# io-board-b-7.net
KiCad netlist of a schematic drawn in EAGLE
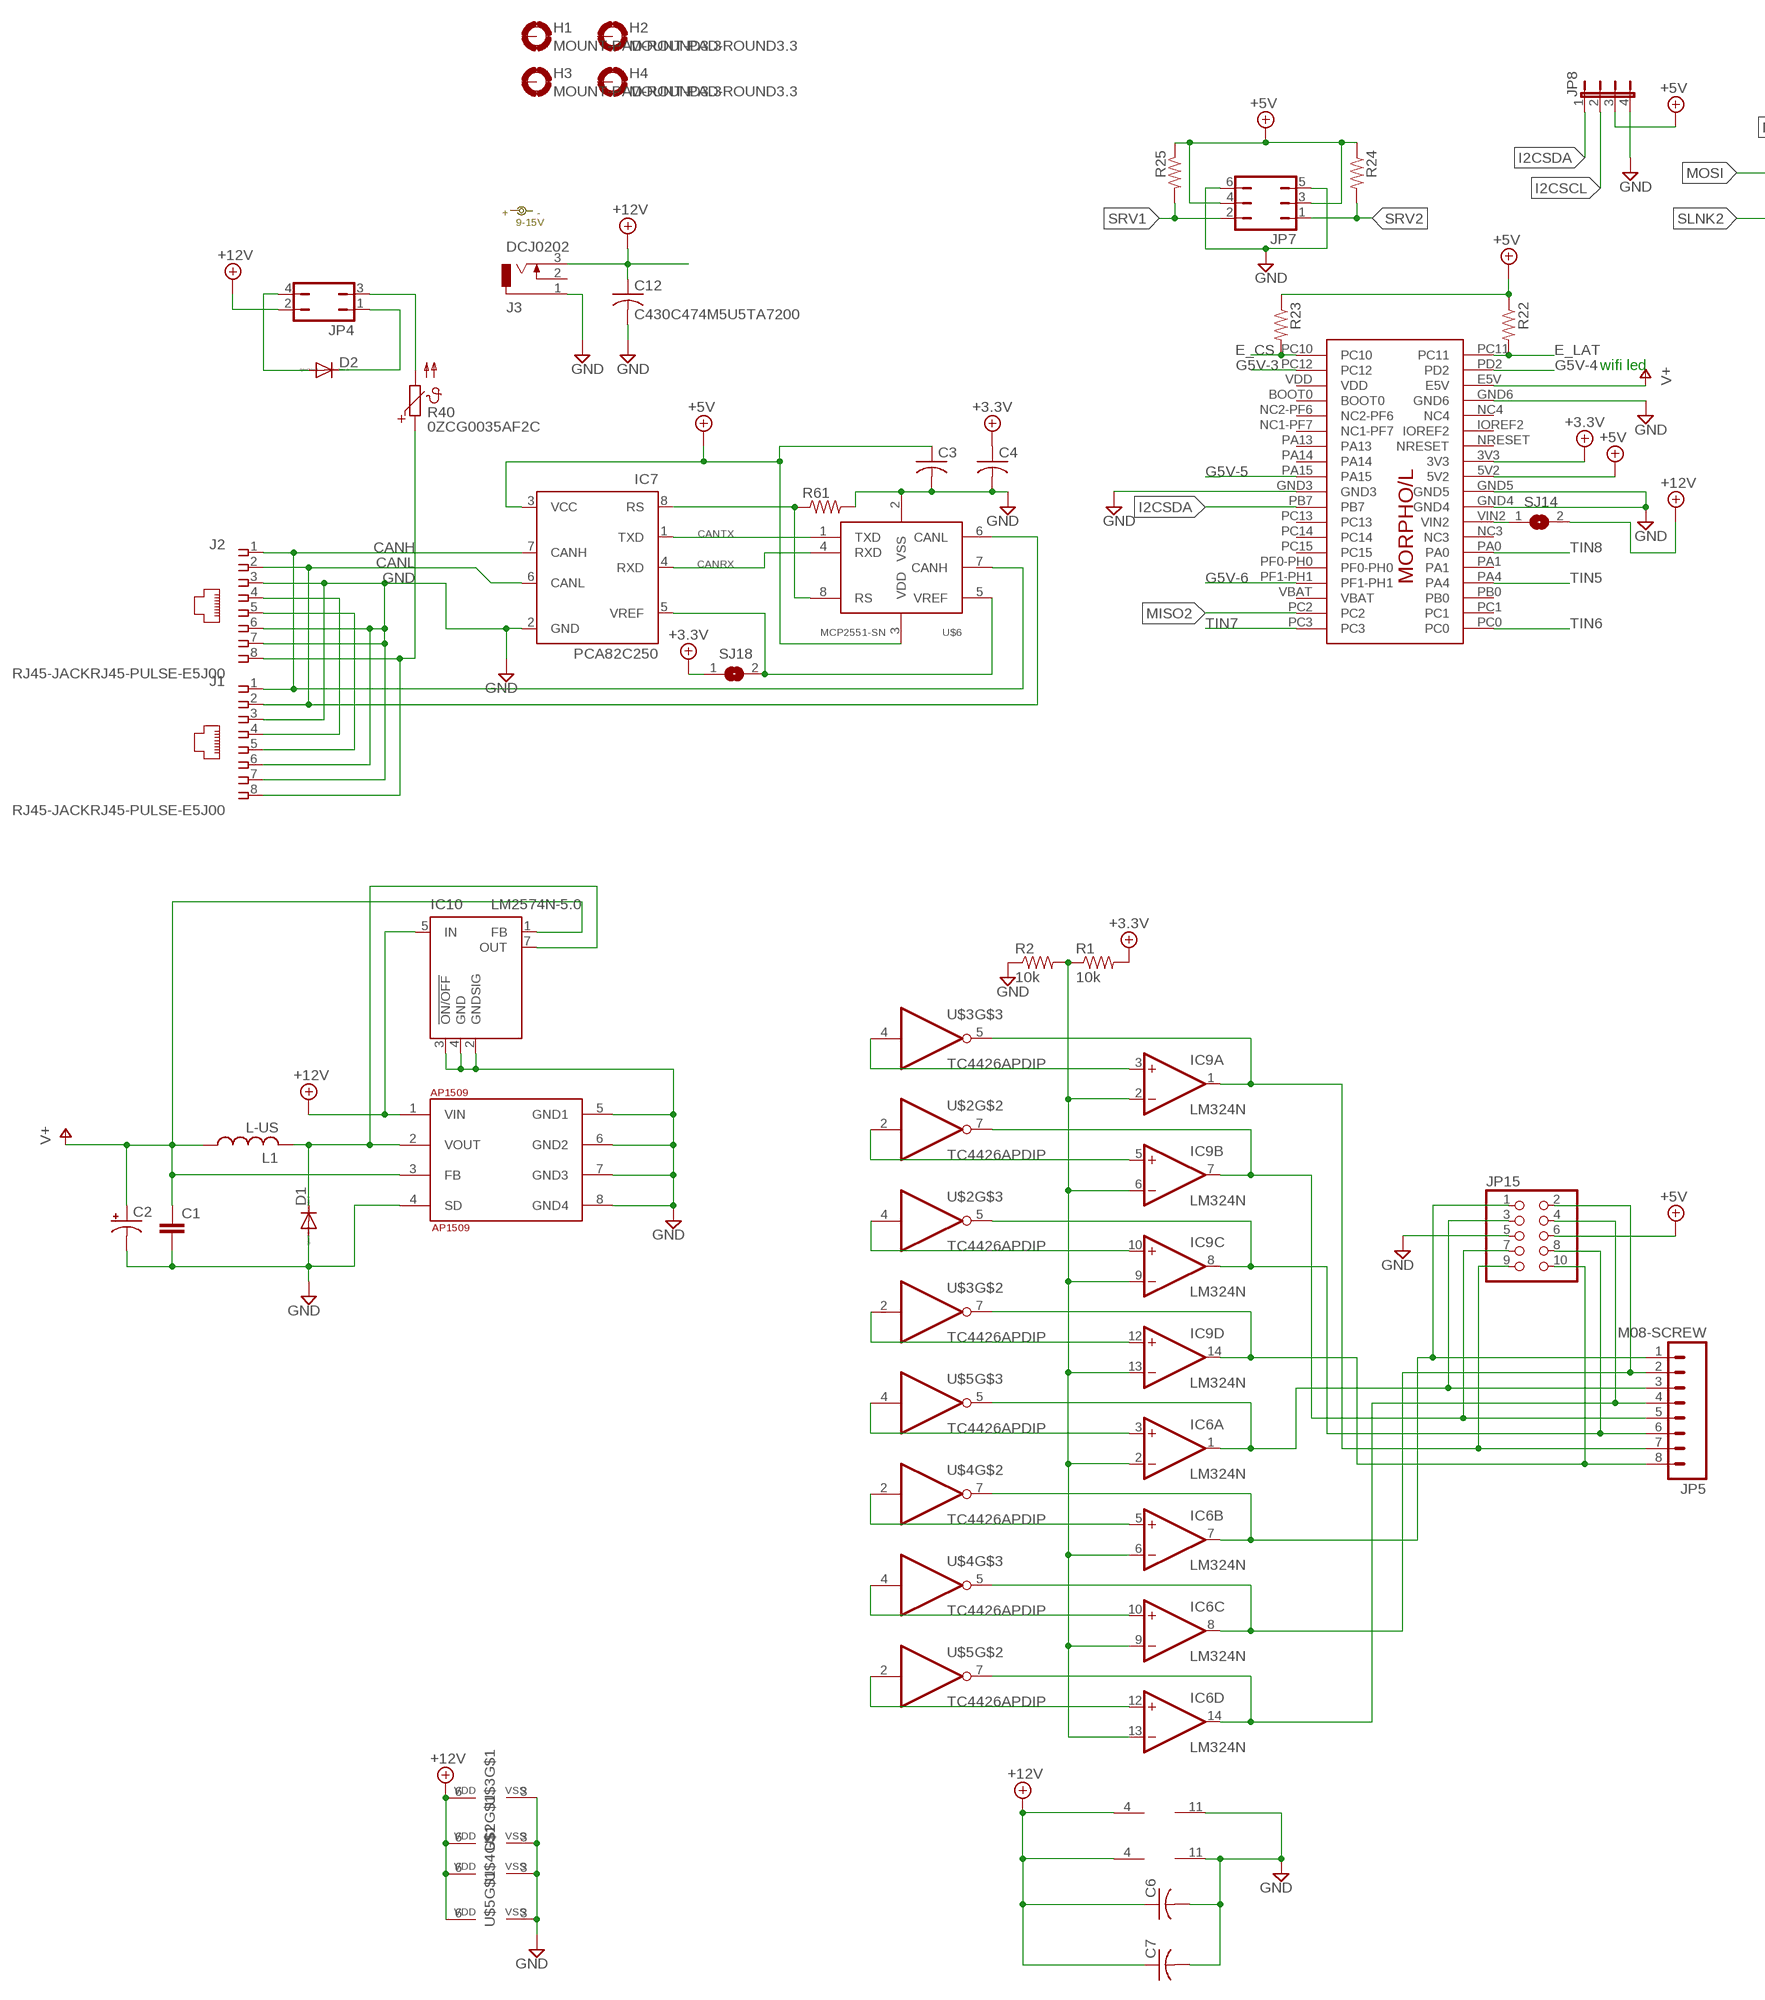
[diagram p0: schematic, sheet 1, part 1 of 2]
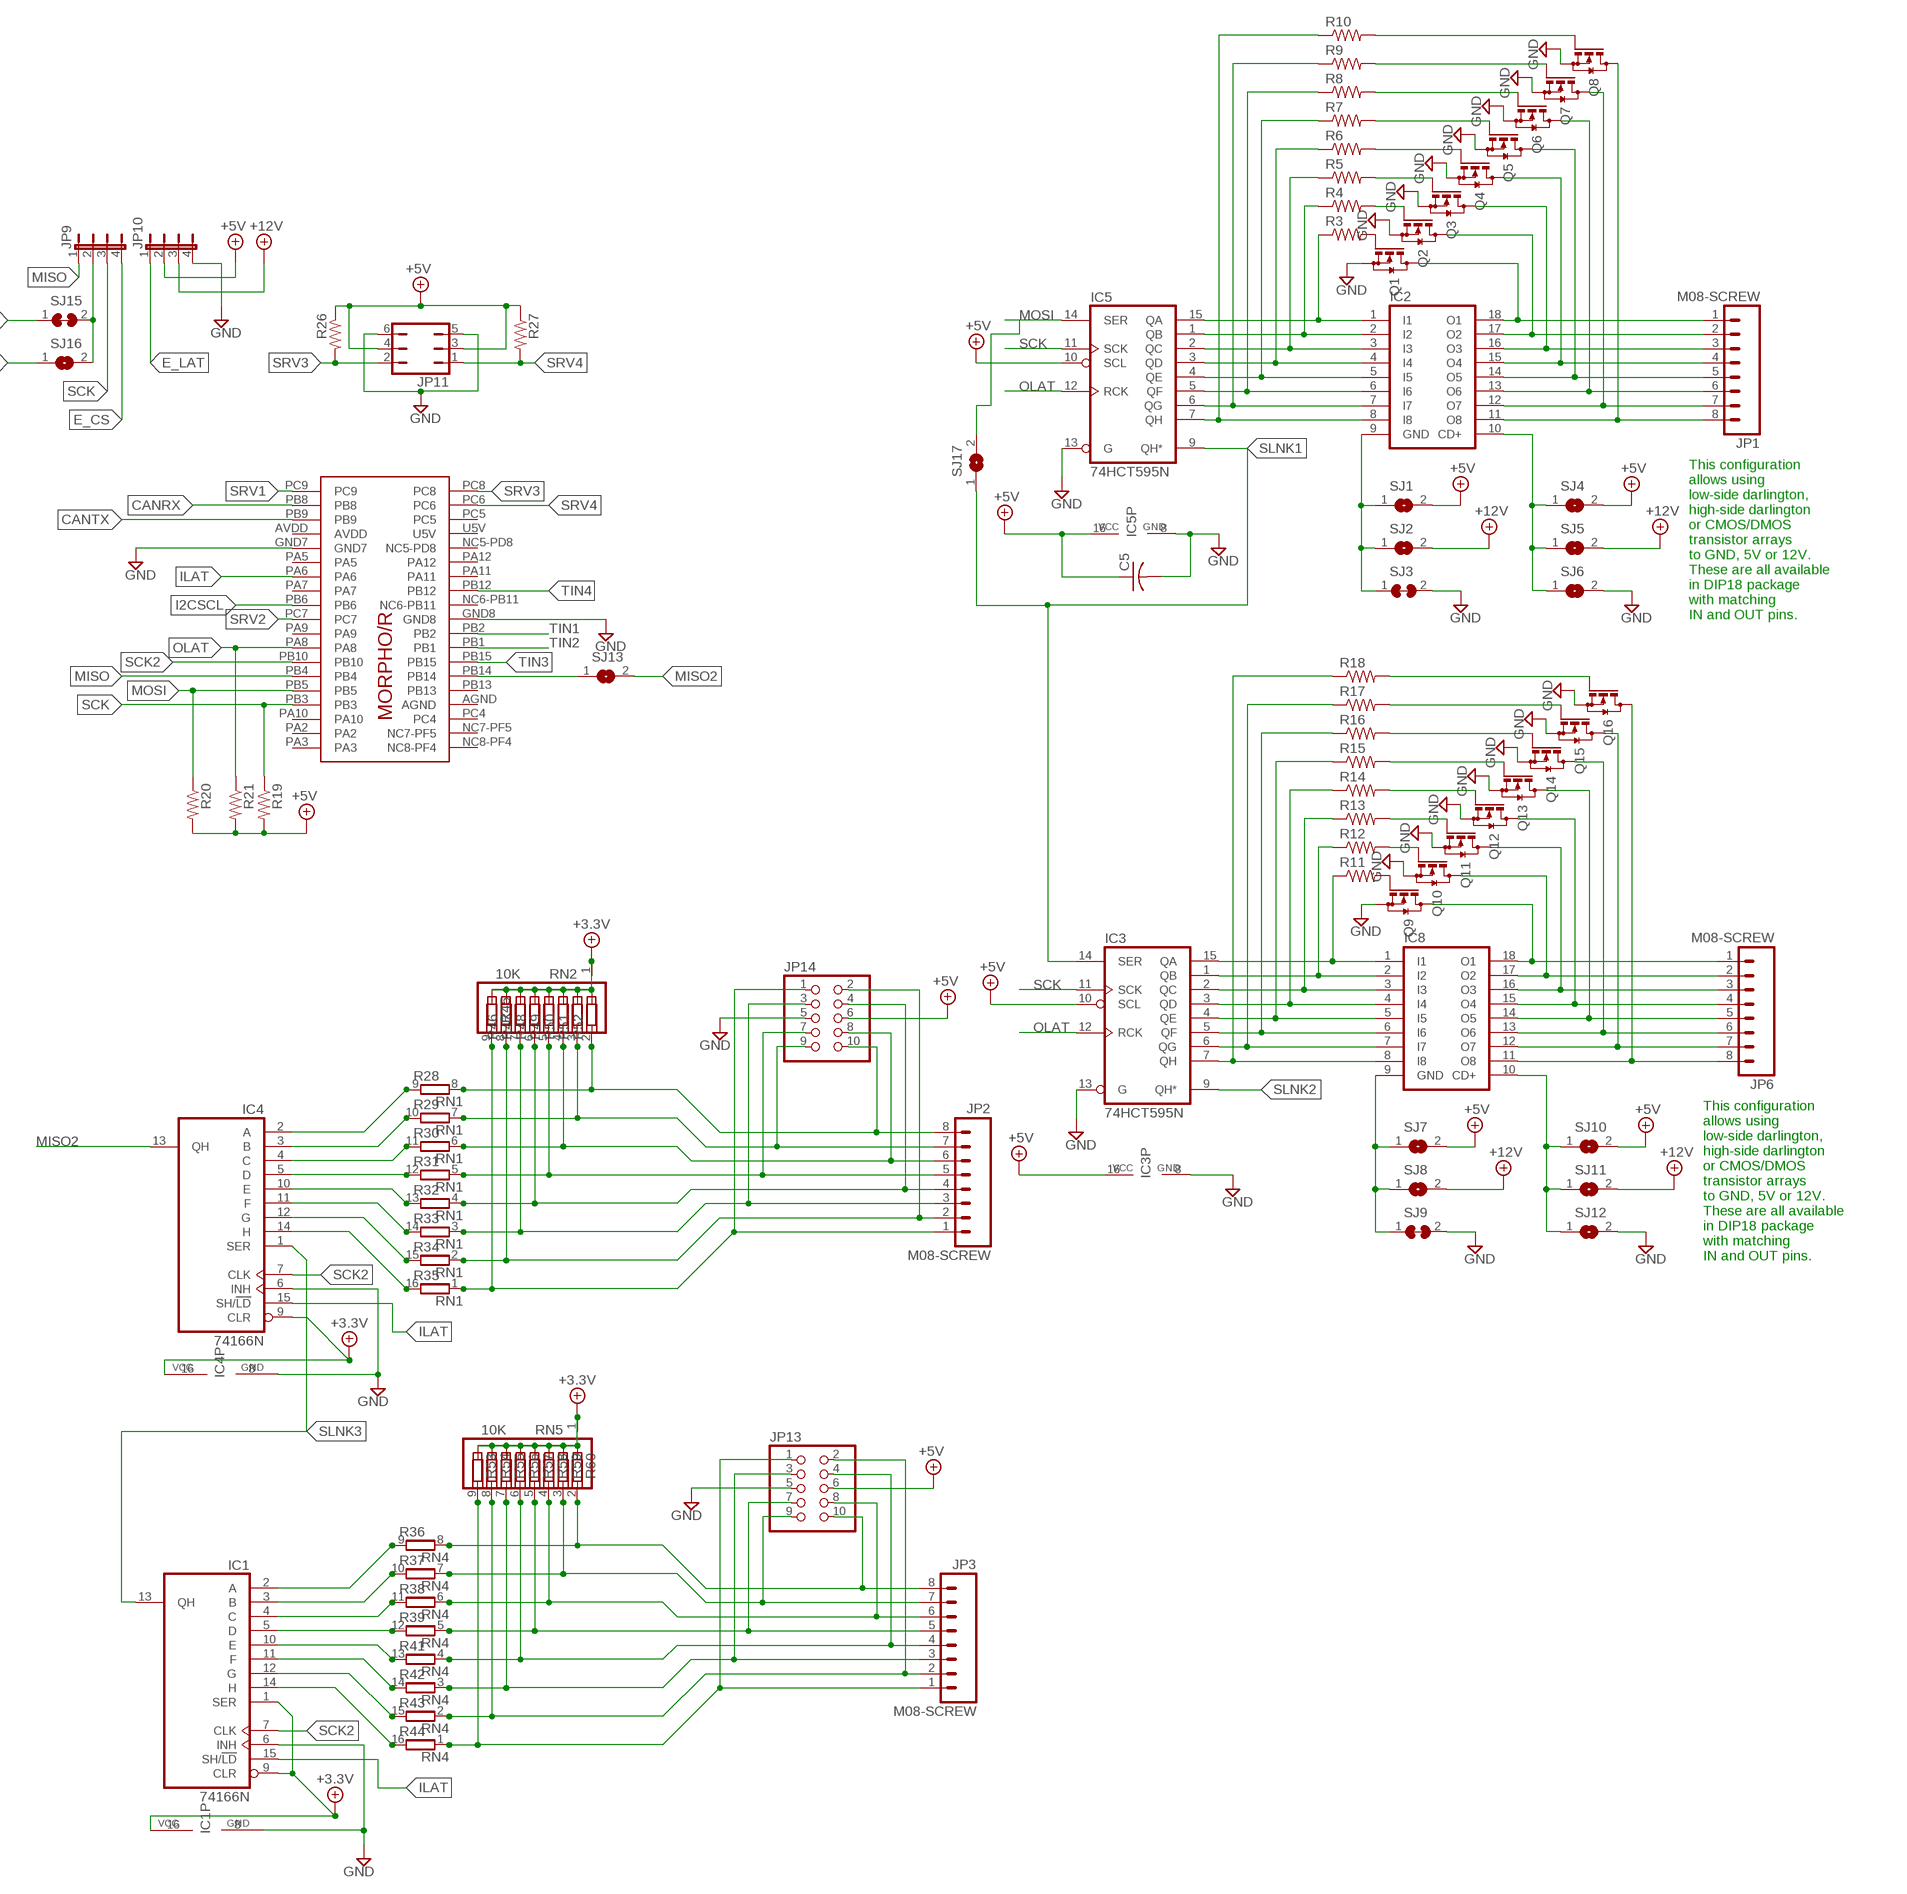
[diagram p1: schematic, sheet 1, part 2 of 2]

(export (version "E")
  (design (tool "Eeschema 10.0.6"))
  (components
    (comp (ref "+12V")
      (value "9-15V")
      (footprint "eagle-import:POWER_USAGE")
      (libsource (lib "eagle-import") (part "DOC-POWER_LABEL"))
    )
    (comp (ref "AP1509")
      (value "AP1509")
      (footprint "eagle-import:SO-08")
      (libsource (lib "eagle-import") (part "AP1509"))
    )
    (comp (ref "C1")
      (value "C-EUC1206")
      (footprint "eagle-import:C1206")
      (libsource (lib "eagle-import") (part "C-EUC1206"))
    )
    (comp (ref "C2")
      (value "CPOL-USE2.5-5")
      (footprint "eagle-import:E2,5-5")
      (libsource (lib "eagle-import") (part "CPOL-USE2.5-5"))
    )
    (comp (ref "C3")
      (value "C-USC0805")
      (footprint "eagle-import:C0805")
      (libsource (lib "eagle-import") (part "C-USC0805"))
    )
    (comp (ref "C4")
      (value "C-USC0805")
      (footprint "eagle-import:C0805")
      (libsource (lib "eagle-import") (part "C-USC0805"))
    )
    (comp (ref "C5")
      (value "C-USC0805")
      (footprint "eagle-import:C0805")
      (libsource (lib "eagle-import") (part "C-USC0805"))
    )
    (comp (ref "C6")
      (value "C-USC1206")
      (footprint "eagle-import:C1206")
      (libsource (lib "eagle-import") (part "C-USC1206"))
    )
    (comp (ref "C7")
      (value "C-USC1206")
      (footprint "eagle-import:C1206")
      (libsource (lib "eagle-import") (part "C-USC1206"))
    )
    (comp (ref "C12")
      (value "C430C474M5U5TA7200")
      (footprint "eagle-import:C075-032X103")
      (libsource (lib "eagle-import") (part "C-US075-032X103"))
    )
    (comp (ref "D1")
      (value "DIODE-DO41-7.6")
      (footprint "eagle-import:DO41-7.6")
      (libsource (lib "eagle-import") (part "DIODE-DO41-7.6"))
    )
    (comp (ref "D2")
      (value "DIODE-DO41-7.6")
      (footprint "eagle-import:DO41-7.6")
      (libsource (lib "eagle-import") (part "DIODE-DO41-7.6"))
    )
    (comp (ref "H1")
      (value "MOUNT-PAD-ROUND3.3")
      (footprint "eagle-import:3,3-PAD")
      (libsource (lib "eagle-import") (part "MOUNT-PAD-ROUND3.3"))
    )
    (comp (ref "H2")
      (value "MOUNT-PAD-ROUND3.3")
      (footprint "eagle-import:3,3-PAD")
      (libsource (lib "eagle-import") (part "MOUNT-PAD-ROUND3.3"))
    )
    (comp (ref "H3")
      (value "MOUNT-PAD-ROUND3.3")
      (footprint "eagle-import:3,3-PAD")
      (libsource (lib "eagle-import") (part "MOUNT-PAD-ROUND3.3"))
    )
    (comp (ref "H4")
      (value "MOUNT-PAD-ROUND3.3")
      (footprint "eagle-import:3,3-PAD")
      (libsource (lib "eagle-import") (part "MOUNT-PAD-ROUND3.3"))
    )
    (comp (ref "IC1")
      (value "74166N")
      (footprint "eagle-import:DIL16")
      (libsource (lib "eagle-import") (part "74166N"))
    )
    (comp (ref "IC2")
      (value "ULN2803A")
      (footprint "eagle-import:DIL18-THIN")
      (libsource (lib "eagle-import") (part "ULN2803A"))
    )
    (comp (ref "IC3")
      (value "74HCT595N")
      (footprint "eagle-import:DIL16")
      (libsource (lib "eagle-import") (part "74595NHCT"))
    )
    (comp (ref "IC4")
      (value "74166N")
      (footprint "eagle-import:DIL16")
      (libsource (lib "eagle-import") (part "74166N"))
    )
    (comp (ref "IC5")
      (value "74HCT595N")
      (footprint "eagle-import:DIL16")
      (libsource (lib "eagle-import") (part "74595NHCT"))
    )
    (comp (ref "IC6")
      (value "LM324N")
      (footprint "eagle-import:DIL14")
      (libsource (lib "eagle-import") (part "LM324N"))
    )
    (comp (ref "IC7")
      (value "PCA82C250")
      (footprint "eagle-import:DIL08")
      (libsource (lib "eagle-import") (part "PCA82C250"))
    )
    (comp (ref "IC8")
      (value "ULN2803A")
      (footprint "eagle-import:DIL18-THIN")
      (libsource (lib "eagle-import") (part "ULN2803A"))
    )
    (comp (ref "IC9")
      (value "LM324N")
      (footprint "eagle-import:DIL14")
      (libsource (lib "eagle-import") (part "LM324N"))
    )
    (comp (ref "IC10")
      (value "LM2574N-5.0")
      (footprint "eagle-import:DIL08")
      (libsource (lib "eagle-import") (part "LM2574?-N5.0"))
    )
    (comp (ref "J1")
      (value "RJ45-JACKRJ45-PULSE-E5J00")
      (footprint "eagle-import:RJ45-PULSE-E5J88")
      (libsource (lib "eagle-import") (part "RJ45-JACKRJ45-PULSE-E5J00"))
    )
    (comp (ref "J2")
      (value "RJ45-JACKRJ45-PULSE-E5J00")
      (footprint "eagle-import:RJ45-PULSE-E5J88")
      (libsource (lib "eagle-import") (part "RJ45-JACKRJ45-PULSE-E5J00"))
    )
    (comp (ref "J3")
      (value "DCJ0202")
      (footprint "eagle-import:DCJ0202")
      (libsource (lib "eagle-import") (part "DCJ0202"))
    )
    (comp (ref "JP1")
      (value "M08-SCREW")
      (footprint "eagle-import:1X08_TERMINAL")
      (libsource (lib "eagle-import") (part "M08-SCREW"))
    )
    (comp (ref "JP2")
      (value "M08-SCREW")
      (footprint "eagle-import:1X08_TERMINAL")
      (libsource (lib "eagle-import") (part "M08-SCREW"))
    )
    (comp (ref "JP3")
      (value "M08-SCREW")
      (footprint "eagle-import:1X08_TERMINAL")
      (libsource (lib "eagle-import") (part "M08-SCREW"))
    )
    (comp (ref "JP4")
      (value "JP2Q")
      (footprint "eagle-import:JP2Q")
      (libsource (lib "eagle-import") (part "JP2Q"))
    )
    (comp (ref "JP5")
      (value "M08-SCREW")
      (footprint "eagle-import:1X08_TERMINAL")
      (libsource (lib "eagle-import") (part "M08-SCREW"))
    )
    (comp (ref "JP6")
      (value "M08-SCREW")
      (footprint "eagle-import:1X08_TERMINAL")
      (libsource (lib "eagle-import") (part "M08-SCREW"))
    )
    (comp (ref "JP7")
      (value "JP3Q")
      (footprint "eagle-import:JP3Q")
      (libsource (lib "eagle-import") (part "JP3Q"))
    )
    (comp (ref "JP8")
      (value "JP4-FLAT")
      (footprint "eagle-import:JP4F")
      (libsource (lib "eagle-import") (part "JP4-FLAT"))
    )
    (comp (ref "JP9")
      (value "JP4-FLAT")
      (footprint "eagle-import:JP4F")
      (libsource (lib "eagle-import") (part "JP4-FLAT"))
    )
    (comp (ref "JP10")
      (value "JP4-FLAT")
      (footprint "eagle-import:JP4F")
      (libsource (lib "eagle-import") (part "JP4-FLAT"))
    )
    (comp (ref "JP11")
      (value "JP3Q")
      (footprint "eagle-import:JP3Q")
      (libsource (lib "eagle-import") (part "JP3Q"))
    )
    (comp (ref "JP13")
      (value "PINHD-2X5CN")
      (footprint "eagle-import:CON10M")
      (libsource (lib "eagle-import") (part "PINHD-2X5CN"))
    )
    (comp (ref "JP14")
      (value "PINHD-2X5CN")
      (footprint "eagle-import:CON10M")
      (libsource (lib "eagle-import") (part "PINHD-2X5CN"))
    )
    (comp (ref "JP15")
      (value "PINHD-2X5CN")
      (footprint "eagle-import:CON10M")
      (libsource (lib "eagle-import") (part "PINHD-2X5CN"))
    )
    (comp (ref "L1")
      (value "L-US")
      (footprint "eagle-import:L5-8,5")
      (libsource (lib "eagle-import") (part "L-US"))
    )
    (comp (ref "Q1")
      (value "BSS123")
      (footprint "eagle-import:SOT23")
      (libsource (lib "eagle-import") (part "BSS123"))
    )
    (comp (ref "Q2")
      (value "BSS123")
      (footprint "eagle-import:SOT23")
      (libsource (lib "eagle-import") (part "BSS123"))
    )
    (comp (ref "Q3")
      (value "BSS123")
      (footprint "eagle-import:SOT23")
      (libsource (lib "eagle-import") (part "BSS123"))
    )
    (comp (ref "Q4")
      (value "BSS123")
      (footprint "eagle-import:SOT23")
      (libsource (lib "eagle-import") (part "BSS123"))
    )
    (comp (ref "Q5")
      (value "BSS123")
      (footprint "eagle-import:SOT23")
      (libsource (lib "eagle-import") (part "BSS123"))
    )
    (comp (ref "Q6")
      (value "BSS123")
      (footprint "eagle-import:SOT23")
      (libsource (lib "eagle-import") (part "BSS123"))
    )
    (comp (ref "Q7")
      (value "BSS123")
      (footprint "eagle-import:SOT23")
      (libsource (lib "eagle-import") (part "BSS123"))
    )
    (comp (ref "Q8")
      (value "BSS123")
      (footprint "eagle-import:SOT23")
      (libsource (lib "eagle-import") (part "BSS123"))
    )
    (comp (ref "Q9")
      (value "BSS123")
      (footprint "eagle-import:SOT23")
      (libsource (lib "eagle-import") (part "BSS123"))
    )
    (comp (ref "Q10")
      (value "BSS123")
      (footprint "eagle-import:SOT23")
      (libsource (lib "eagle-import") (part "BSS123"))
    )
    (comp (ref "Q11")
      (value "BSS123")
      (footprint "eagle-import:SOT23")
      (libsource (lib "eagle-import") (part "BSS123"))
    )
    (comp (ref "Q12")
      (value "BSS123")
      (footprint "eagle-import:SOT23")
      (libsource (lib "eagle-import") (part "BSS123"))
    )
    (comp (ref "Q13")
      (value "BSS123")
      (footprint "eagle-import:SOT23")
      (libsource (lib "eagle-import") (part "BSS123"))
    )
    (comp (ref "Q14")
      (value "BSS123")
      (footprint "eagle-import:SOT23")
      (libsource (lib "eagle-import") (part "BSS123"))
    )
    (comp (ref "Q15")
      (value "BSS123")
      (footprint "eagle-import:SOT23")
      (libsource (lib "eagle-import") (part "BSS123"))
    )
    (comp (ref "Q16")
      (value "BSS123")
      (footprint "eagle-import:SOT23")
      (libsource (lib "eagle-import") (part "BSS123"))
    )
    (comp (ref "R1")
      (value "10k")
      (footprint "eagle-import:R0805")
      (libsource (lib "eagle-import") (part "R-US_R0805"))
    )
    (comp (ref "R2")
      (value "10k")
      (footprint "eagle-import:R0805")
      (libsource (lib "eagle-import") (part "R-US_R0805"))
    )
    (comp (ref "R3")
      (value "R-US_R0603")
      (footprint "eagle-import:R0603")
      (libsource (lib "eagle-import") (part "R-US_R0603"))
    )
    (comp (ref "R4")
      (value "R-US_R0603")
      (footprint "eagle-import:R0603")
      (libsource (lib "eagle-import") (part "R-US_R0603"))
    )
    (comp (ref "R5")
      (value "R-US_R0603")
      (footprint "eagle-import:R0603")
      (libsource (lib "eagle-import") (part "R-US_R0603"))
    )
    (comp (ref "R6")
      (value "R-US_R0603")
      (footprint "eagle-import:R0603")
      (libsource (lib "eagle-import") (part "R-US_R0603"))
    )
    (comp (ref "R7")
      (value "R-US_R0603")
      (footprint "eagle-import:R0603")
      (libsource (lib "eagle-import") (part "R-US_R0603"))
    )
    (comp (ref "R8")
      (value "R-US_R0603")
      (footprint "eagle-import:R0603")
      (libsource (lib "eagle-import") (part "R-US_R0603"))
    )
    (comp (ref "R9")
      (value "R-US_R0603")
      (footprint "eagle-import:R0603")
      (libsource (lib "eagle-import") (part "R-US_R0603"))
    )
    (comp (ref "R10")
      (value "R-US_R0603")
      (footprint "eagle-import:R0603")
      (libsource (lib "eagle-import") (part "R-US_R0603"))
    )
    (comp (ref "R11")
      (value "R-US_R0603")
      (footprint "eagle-import:R0603")
      (libsource (lib "eagle-import") (part "R-US_R0603"))
    )
    (comp (ref "R12")
      (value "R-US_R0603")
      (footprint "eagle-import:R0603")
      (libsource (lib "eagle-import") (part "R-US_R0603"))
    )
    (comp (ref "R13")
      (value "R-US_R0603")
      (footprint "eagle-import:R0603")
      (libsource (lib "eagle-import") (part "R-US_R0603"))
    )
    (comp (ref "R14")
      (value "R-US_R0603")
      (footprint "eagle-import:R0603")
      (libsource (lib "eagle-import") (part "R-US_R0603"))
    )
    (comp (ref "R15")
      (value "R-US_R0603")
      (footprint "eagle-import:R0603")
      (libsource (lib "eagle-import") (part "R-US_R0603"))
    )
    (comp (ref "R16")
      (value "R-US_R0603")
      (footprint "eagle-import:R0603")
      (libsource (lib "eagle-import") (part "R-US_R0603"))
    )
    (comp (ref "R17")
      (value "R-US_R0603")
      (footprint "eagle-import:R0603")
      (libsource (lib "eagle-import") (part "R-US_R0603"))
    )
    (comp (ref "R18")
      (value "R-US_R0603")
      (footprint "eagle-import:R0603")
      (libsource (lib "eagle-import") (part "R-US_R0603"))
    )
    (comp (ref "R19")
      (value "R-US_R0805")
      (footprint "eagle-import:R0805")
      (libsource (lib "eagle-import") (part "rcl_334_R-US_R0805"))
    )
    (comp (ref "R20")
      (value "R-US_R0805")
      (footprint "eagle-import:R0805")
      (libsource (lib "eagle-import") (part "rcl_334_R-US_R0805"))
    )
    (comp (ref "R21")
      (value "R-US_R0805")
      (footprint "eagle-import:R0805")
      (libsource (lib "eagle-import") (part "rcl_334_R-US_R0805"))
    )
    (comp (ref "R22")
      (value "R-US_R0805")
      (footprint "eagle-import:R0805")
      (libsource (lib "eagle-import") (part "rcl_334_R-US_R0805"))
    )
    (comp (ref "R23")
      (value "R-US_R0805")
      (footprint "eagle-import:R0805")
      (libsource (lib "eagle-import") (part "rcl_334_R-US_R0805"))
    )
    (comp (ref "R24")
      (value "R-US_R0805")
      (footprint "eagle-import:R0805")
      (libsource (lib "eagle-import") (part "rcl_334_R-US_R0805"))
    )
    (comp (ref "R25")
      (value "R-US_R0805")
      (footprint "eagle-import:R0805")
      (libsource (lib "eagle-import") (part "rcl_334_R-US_R0805"))
    )
    (comp (ref "R26")
      (value "R-US_R0805")
      (footprint "eagle-import:R0805")
      (libsource (lib "eagle-import") (part "rcl_334_R-US_R0805"))
    )
    (comp (ref "R27")
      (value "R-US_R0805")
      (footprint "eagle-import:R0805")
      (libsource (lib "eagle-import") (part "rcl_334_R-US_R0805"))
    )
    (comp (ref "R28")
      (value "R-EU_R0603")
      (footprint "eagle-import:R0603")
      (libsource (lib "eagle-import") (part "R-EU_R0603"))
    )
    (comp (ref "R29")
      (value "R-EU_R0603")
      (footprint "eagle-import:R0603")
      (libsource (lib "eagle-import") (part "R-EU_R0603"))
    )
    (comp (ref "R30")
      (value "R-EU_R0603")
      (footprint "eagle-import:R0603")
      (libsource (lib "eagle-import") (part "R-EU_R0603"))
    )
    (comp (ref "R31")
      (value "R-EU_R0603")
      (footprint "eagle-import:R0603")
      (libsource (lib "eagle-import") (part "R-EU_R0603"))
    )
    (comp (ref "R32")
      (value "R-EU_R0603")
      (footprint "eagle-import:R0603")
      (libsource (lib "eagle-import") (part "R-EU_R0603"))
    )
    (comp (ref "R33")
      (value "R-EU_R0603")
      (footprint "eagle-import:R0603")
      (libsource (lib "eagle-import") (part "R-EU_R0603"))
    )
    (comp (ref "R34")
      (value "R-EU_R0603")
      (footprint "eagle-import:R0603")
      (libsource (lib "eagle-import") (part "R-EU_R0603"))
    )
    (comp (ref "R35")
      (value "R-EU_R0603")
      (footprint "eagle-import:R0603")
      (libsource (lib "eagle-import") (part "R-EU_R0603"))
    )
    (comp (ref "R36")
      (value "R-EU_R0603")
      (footprint "eagle-import:R0603")
      (libsource (lib "eagle-import") (part "R-EU_R0603"))
    )
    (comp (ref "R37")
      (value "R-EU_R0603")
      (footprint "eagle-import:R0603")
      (libsource (lib "eagle-import") (part "R-EU_R0603"))
    )
    (comp (ref "R38")
      (value "R-EU_R0603")
      (footprint "eagle-import:R0603")
      (libsource (lib "eagle-import") (part "R-EU_R0603"))
    )
    (comp (ref "R39")
      (value "R-EU_R0603")
      (footprint "eagle-import:R0603")
      (libsource (lib "eagle-import") (part "R-EU_R0603"))
    )
    (comp (ref "R40")
      (value "0ZCG0035AF2C")
      (footprint "eagle-import:PTC1812")
      (libsource (lib "eagle-import") (part "PTC_1812"))
    )
    (comp (ref "R41")
      (value "R-EU_R0603")
      (footprint "eagle-import:R0603")
      (libsource (lib "eagle-import") (part "R-EU_R0603"))
    )
    (comp (ref "R42")
      (value "R-EU_R0603")
      (footprint "eagle-import:R0603")
      (libsource (lib "eagle-import") (part "R-EU_R0603"))
    )
    (comp (ref "R43")
      (value "R-EU_R0603")
      (footprint "eagle-import:R0603")
      (libsource (lib "eagle-import") (part "R-EU_R0603"))
    )
    (comp (ref "R44")
      (value "R-EU_R0603")
      (footprint "eagle-import:R0603")
      (libsource (lib "eagle-import") (part "R-EU_R0603"))
    )
    (comp (ref "R45")
      (value "R-EU_R0603")
      (footprint "eagle-import:R0603")
      (libsource (lib "eagle-import") (part "R-EU_R0603"))
    )
    (comp (ref "R46")
      (value "R-EU_R0603")
      (footprint "eagle-import:R0603")
      (libsource (lib "eagle-import") (part "R-EU_R0603"))
    )
    (comp (ref "R47")
      (value "R-EU_R0603")
      (footprint "eagle-import:R0603")
      (libsource (lib "eagle-import") (part "R-EU_R0603"))
    )
    (comp (ref "R48")
      (value "R-EU_R0603")
      (footprint "eagle-import:R0603")
      (libsource (lib "eagle-import") (part "R-EU_R0603"))
    )
    (comp (ref "R49")
      (value "R-EU_R0603")
      (footprint "eagle-import:R0603")
      (libsource (lib "eagle-import") (part "R-EU_R0603"))
    )
    (comp (ref "R50")
      (value "R-EU_R0603")
      (footprint "eagle-import:R0603")
      (libsource (lib "eagle-import") (part "R-EU_R0603"))
    )
    (comp (ref "R51")
      (value "R-EU_R0603")
      (footprint "eagle-import:R0603")
      (libsource (lib "eagle-import") (part "R-EU_R0603"))
    )
    (comp (ref "R52")
      (value "R-EU_R0603")
      (footprint "eagle-import:R0603")
      (libsource (lib "eagle-import") (part "R-EU_R0603"))
    )
    (comp (ref "R53")
      (value "R-EU_R0603")
      (footprint "eagle-import:R0603")
      (libsource (lib "eagle-import") (part "R-EU_R0603"))
    )
    (comp (ref "R54")
      (value "R-EU_R0603")
      (footprint "eagle-import:R0603")
      (libsource (lib "eagle-import") (part "R-EU_R0603"))
    )
    (comp (ref "R55")
      (value "R-EU_R0603")
      (footprint "eagle-import:R0603")
      (libsource (lib "eagle-import") (part "R-EU_R0603"))
    )
    (comp (ref "R56")
      (value "R-EU_R0603")
      (footprint "eagle-import:R0603")
      (libsource (lib "eagle-import") (part "R-EU_R0603"))
    )
    (comp (ref "R57")
      (value "R-EU_R0603")
      (footprint "eagle-import:R0603")
      (libsource (lib "eagle-import") (part "R-EU_R0603"))
    )
    (comp (ref "R58")
      (value "R-EU_R0603")
      (footprint "eagle-import:R0603")
      (libsource (lib "eagle-import") (part "R-EU_R0603"))
    )
    (comp (ref "R59")
      (value "R-EU_R0603")
      (footprint "eagle-import:R0603")
      (libsource (lib "eagle-import") (part "R-EU_R0603"))
    )
    (comp (ref "R60")
      (value "R-EU_R0603")
      (footprint "eagle-import:R0603")
      (libsource (lib "eagle-import") (part "R-EU_R0603"))
    )
    (comp (ref "R61")
      (value "R-US_R0805")
      (footprint "eagle-import:R0805")
      (libsource (lib "eagle-import") (part "rcl_334_R-US_R0805"))
    )
    (comp (ref "RN1")
      (value "8R-P")
      (footprint "eagle-import:DIL16")
      (libsource (lib "eagle-import") (part "8R-P"))
    )
    (comp (ref "RN2")
      (value "10K")
      (footprint "eagle-import:SIL9")
      (libsource (lib "eagle-import") (part "G08R"))
    )
    (comp (ref "RN4")
      (value "8R-P")
      (footprint "eagle-import:DIL16")
      (libsource (lib "eagle-import") (part "8R-P"))
    )
    (comp (ref "RN5")
      (value "10K")
      (footprint "eagle-import:SIL9")
      (libsource (lib "eagle-import") (part "G08R"))
    )
    (comp (ref "SJ1")
      (value "SJ")
      (footprint "eagle-import:SJ-RND")
      (libsource (lib "eagle-import") (part "SJ"))
    )
    (comp (ref "SJ2")
      (value "SJ")
      (footprint "eagle-import:SJ-RND")
      (libsource (lib "eagle-import") (part "SJ"))
    )
    (comp (ref "SJ3")
      (value "SJ-C")
      (footprint "eagle-import:SJW-C")
      (libsource (lib "eagle-import") (part "SJ-C"))
    )
    (comp (ref "SJ4")
      (value "SJ")
      (footprint "eagle-import:SJ-RND")
      (libsource (lib "eagle-import") (part "SJ"))
    )
    (comp (ref "SJ5")
      (value "SJ")
      (footprint "eagle-import:SJ-RND")
      (libsource (lib "eagle-import") (part "SJ"))
    )
    (comp (ref "SJ6")
      (value "SJ")
      (footprint "eagle-import:SJ-RND")
      (libsource (lib "eagle-import") (part "SJ"))
    )
    (comp (ref "SJ7")
      (value "SJ")
      (footprint "eagle-import:SJ-RND")
      (libsource (lib "eagle-import") (part "SJ"))
    )
    (comp (ref "SJ8")
      (value "SJ")
      (footprint "eagle-import:SJ-RND")
      (libsource (lib "eagle-import") (part "SJ"))
    )
    (comp (ref "SJ9")
      (value "SJ-C")
      (footprint "eagle-import:SJW-C")
      (libsource (lib "eagle-import") (part "SJ-C"))
    )
    (comp (ref "SJ10")
      (value "SJ")
      (footprint "eagle-import:SJ-RND")
      (libsource (lib "eagle-import") (part "SJ"))
    )
    (comp (ref "SJ11")
      (value "SJ")
      (footprint "eagle-import:SJ-RND")
      (libsource (lib "eagle-import") (part "SJ"))
    )
    (comp (ref "SJ12")
      (value "SJ")
      (footprint "eagle-import:SJ-RND")
      (libsource (lib "eagle-import") (part "SJ"))
    )
    (comp (ref "SJ13")
      (value "SJ")
      (footprint "eagle-import:SJ-RND")
      (libsource (lib "eagle-import") (part "SJ"))
    )
    (comp (ref "SJ14")
      (value "SJ")
      (footprint "eagle-import:SJ-RND")
      (libsource (lib "eagle-import") (part "SJ"))
    )
    (comp (ref "SJ15")
      (value "SJ-C")
      (footprint "eagle-import:SJW-C")
      (libsource (lib "eagle-import") (part "SJ-C"))
    )
    (comp (ref "SJ16")
      (value "SJ")
      (footprint "eagle-import:SJ-RND")
      (libsource (lib "eagle-import") (part "SJ"))
    )
    (comp (ref "SJ17")
      (value "SJ")
      (footprint "eagle-import:SJ-RND")
      (libsource (lib "eagle-import") (part "SJ"))
    )
    (comp (ref "SJ18")
      (value "SJ")
      (footprint "eagle-import:SJ-RND")
      (libsource (lib "eagle-import") (part "SJ"))
    )
    (comp (ref "U$1")
      (value "NUCLEO_64_GENERIC")
      (footprint "eagle-import:NUCLEO_BRD_BASE64")
      (libsource (lib "eagle-import") (part "NUCLEO_64_GENERIC"))
    )
    (comp (ref "U$2")
      (value "TC4426APDIP")
      (footprint "eagle-import:DIL08-LONG")
      (libsource (lib "eagle-import") (part "TC4426APDIP"))
    )
    (comp (ref "U$3")
      (value "TC4426APDIP")
      (footprint "eagle-import:DIL08-LONG")
      (libsource (lib "eagle-import") (part "TC4426APDIP"))
    )
    (comp (ref "U$4")
      (value "TC4426APDIP")
      (footprint "eagle-import:DIL08-LONG")
      (libsource (lib "eagle-import") (part "TC4426APDIP"))
    )
    (comp (ref "U$5")
      (value "TC4426APDIP")
      (footprint "eagle-import:DIL08-LONG")
      (libsource (lib "eagle-import") (part "TC4426APDIP"))
    )
    (comp (ref "U$6")
      (value "MCP2551-SN")
      (footprint "eagle-import:SO-08")
      (libsource (lib "eagle-import") (part "MCP2551-SN"))
    )
  )
  (nets
    (net (code "1") (name "+3.3V") (class "Default")
      (node (ref "C4") (pin "1") (pinfunction "1_1") (pintype "passive"))
      (node (ref "IC1") (pin "1") (pinfunction "SER_1") (pintype "input"))
      (node (ref "IC1") (pin "16") (pinfunction "VCC_16") (pintype "power_in"))
      (node (ref "IC1") (pin "9") (pinfunction "CLR_9") (pintype "input"))
      (node (ref "IC4") (pin "16") (pinfunction "VCC_16") (pintype "power_in"))
      (node (ref "IC4") (pin "9") (pinfunction "CLR_9") (pintype "input"))
      (node (ref "R1") (pin "2") (pinfunction "2_2") (pintype "passive"))
      (node (ref "R45") (pin "1") (pinfunction "1_1") (pintype "passive"))
      (node (ref "R46") (pin "2") (pinfunction "2_2") (pintype "passive"))
      (node (ref "R47") (pin "2") (pinfunction "2_2") (pintype "passive"))
      (node (ref "R48") (pin "2") (pinfunction "2_2") (pintype "passive"))
      (node (ref "R49") (pin "2") (pinfunction "2_2") (pintype "passive"))
      (node (ref "R50") (pin "2") (pinfunction "2_2") (pintype "passive"))
      (node (ref "R51") (pin "2") (pinfunction "2_2") (pintype "passive"))
      (node (ref "R52") (pin "2") (pinfunction "2_2") (pintype "passive"))
      (node (ref "R53") (pin "1") (pinfunction "1_1") (pintype "passive"))
      (node (ref "R54") (pin "1") (pinfunction "1_1") (pintype "passive"))
      (node (ref "R55") (pin "1") (pinfunction "1_1") (pintype "passive"))
      (node (ref "R56") (pin "1") (pinfunction "1_1") (pintype "passive"))
      (node (ref "R57") (pin "1") (pinfunction "1_1") (pintype "passive"))
      (node (ref "R58") (pin "1") (pinfunction "1_1") (pintype "passive"))
      (node (ref "R59") (pin "1") (pinfunction "1_1") (pintype "passive"))
      (node (ref "R60") (pin "1") (pinfunction "1_1") (pintype "passive"))
      (node (ref "RN2") (pin "1") (pinfunction "1_1") (pintype "passive"))
      (node (ref "RN5") (pin "1") (pinfunction "1_1") (pintype "passive"))
      (node (ref "SJ18") (pin "1") (pinfunction "1_1") (pintype "passive"))
      (node (ref "U$1") (pin "3V3") (pinfunction "3V3_3V3") (pintype "power_in"))
    )
    (net (code "2") (name "+5V") (class "Default")
      (node (ref "C3") (pin "1") (pinfunction "1_1") (pintype "passive"))
      (node (ref "C5") (pin "1") (pinfunction "1_1") (pintype "passive"))
      (node (ref "IC3") (pin "10") (pinfunction "SCL_10") (pintype "input"))
      (node (ref "IC3") (pin "16") (pinfunction "VCC_16") (pintype "power_in"))
      (node (ref "IC5") (pin "10") (pinfunction "SCL_10") (pintype "input"))
      (node (ref "IC5") (pin "16") (pinfunction "VCC_16") (pintype "power_in"))
      (node (ref "IC7") (pin "3") (pinfunction "VCC_3") (pintype "power_in"))
      (node (ref "JP10") (pin "2") (pinfunction "2_2") (pintype "passive"))
      (node (ref "JP11") (pin "3") (pinfunction "3_3") (pintype "passive"))
      (node (ref "JP11") (pin "4") (pinfunction "4_4") (pintype "passive"))
      (node (ref "JP13") (pin "6") (pinfunction "6_6") (pintype "passive"))
      (node (ref "JP14") (pin "6") (pinfunction "6_6") (pintype "passive"))
      (node (ref "JP15") (pin "6") (pinfunction "6_6") (pintype "passive"))
      (node (ref "JP7") (pin "3") (pinfunction "3_3") (pintype "passive"))
      (node (ref "JP7") (pin "4") (pinfunction "4_4") (pintype "passive"))
      (node (ref "JP8") (pin "3") (pinfunction "3_3") (pintype "passive"))
      (node (ref "R19") (pin "2") (pinfunction "2_2") (pintype "passive"))
      (node (ref "R20") (pin "2") (pinfunction "2_2") (pintype "passive"))
      (node (ref "R21") (pin "2") (pinfunction "2_2") (pintype "passive"))
      (node (ref "R22") (pin "1") (pinfunction "1_1") (pintype "passive"))
      (node (ref "R23") (pin "1") (pinfunction "1_1") (pintype "passive"))
      (node (ref "R24") (pin "1") (pinfunction "1_1") (pintype "passive"))
      (node (ref "R25") (pin "1") (pinfunction "1_1") (pintype "passive"))
      (node (ref "R26") (pin "1") (pinfunction "1_1") (pintype "passive"))
      (node (ref "R27") (pin "1") (pinfunction "1_1") (pintype "passive"))
      (node (ref "SJ1") (pin "2") (pinfunction "2_2") (pintype "passive"))
      (node (ref "SJ10") (pin "2") (pinfunction "2_2") (pintype "passive"))
      (node (ref "SJ4") (pin "2") (pinfunction "2_2") (pintype "passive"))
      (node (ref "SJ7") (pin "2") (pinfunction "2_2") (pintype "passive"))
      (node (ref "U$1") (pin "5V2") (pinfunction "5V2_5V2") (pintype "power_in"))
      (node (ref "U$6") (pin "3") (pinfunction "VDD_3") (pintype "power_in"))
    )
    (net (code "3") (name "+12V") (class "Default")
      (node (ref "AP1509") (pin "1") (pinfunction "VIN_1") (pintype "bidirectional"))
      (node (ref "C12") (pin "1") (pinfunction "1_1") (pintype "passive"))
      (node (ref "C6") (pin "1") (pinfunction "1_1") (pintype "passive"))
      (node (ref "C7") (pin "1") (pinfunction "1_1") (pintype "passive"))
      (node (ref "IC10") (pin "5") (pinfunction "IN_5") (pintype "input"))
      (node (ref "IC6") (pin "4") (pinfunction "V+_4") (pintype "power_in"))
      (node (ref "IC9") (pin "4") (pinfunction "V+_4") (pintype "power_in"))
      (node (ref "J3") (pin "3") (pinfunction "3_3") (pintype "passive"))
      (node (ref "JP10") (pin "3") (pinfunction "3_3") (pintype "passive"))
      (node (ref "JP4") (pin "2") (pinfunction "2_2") (pintype "passive"))
      (node (ref "SJ11") (pin "2") (pinfunction "2_2") (pintype "passive"))
      (node (ref "SJ14") (pin "2") (pinfunction "2_2") (pintype "passive"))
      (node (ref "SJ2") (pin "2") (pinfunction "2_2") (pintype "passive"))
      (node (ref "SJ5") (pin "2") (pinfunction "2_2") (pintype "passive"))
      (node (ref "SJ8") (pin "2") (pinfunction "2_2") (pintype "passive"))
      (node (ref "U$2") (pin "6") (pinfunction "VDD_6") (pintype "power_in"))
      (node (ref "U$3") (pin "6") (pinfunction "VDD_6") (pintype "power_in"))
      (node (ref "U$4") (pin "6") (pinfunction "VDD_6") (pintype "power_in"))
      (node (ref "U$5") (pin "6") (pinfunction "VDD_6") (pintype "power_in"))
    )
    (net (code "4") (name "/AGND") (class "Default")
      (node (ref "U$1") (pin "AGND") (pinfunction "AGND_AGND") (pintype "power_in"))
    )
    (net (code "5") (name "/AVDD") (class "Default")
      (node (ref "U$1") (pin "AVDD") (pinfunction "AVDD_AVDD") (pintype "power_in"))
    )
    (net (code "6") (name "/CANH") (class "Default")
      (node (ref "IC7") (pin "7") (pinfunction "CANH_7") (pintype "bidirectional"))
      (node (ref "J1") (pin "1") (pinfunction "1_1") (pintype "passive"))
      (node (ref "J2") (pin "1") (pinfunction "1_1") (pintype "passive"))
      (node (ref "U$6") (pin "7") (pinfunction "CANH_7") (pintype "bidirectional"))
    )
    (net (code "7") (name "/CANL") (class "Default")
      (node (ref "IC7") (pin "6") (pinfunction "CANL_6") (pintype "bidirectional"))
      (node (ref "J1") (pin "2") (pinfunction "2_2") (pintype "passive"))
      (node (ref "J2") (pin "2") (pinfunction "2_2") (pintype "passive"))
      (node (ref "U$6") (pin "6") (pinfunction "CANL_6") (pintype "bidirectional"))
    )
    (net (code "8") (name "/G5V-3") (class "Default")
      (node (ref "U$1") (pin "PC12") (pinfunction "PC12_PC12") (pintype "bidirectional"))
    )
    (net (code "9") (name "/G5V-4") (class "Default")
      (node (ref "U$1") (pin "PD2") (pinfunction "PD2_PD2") (pintype "bidirectional"))
    )
    (net (code "10") (name "/G5V-5") (class "Default")
      (node (ref "U$1") (pin "PA15") (pinfunction "PA15_PA15") (pintype "bidirectional"))
    )
    (net (code "11") (name "/G5V-6") (class "Default")
      (node (ref "U$1") (pin "PF1-PH1") (pinfunction "PF1-PH1_PF1-PH1") (pintype "bidirectional"))
    )
    (net (code "12") (name "/TIN1") (class "Default")
      (node (ref "IC9") (pin "3") (pinfunction "+IN_3") (pintype "input"))
      (node (ref "U$1") (pin "PB2") (pinfunction "PB2_PB2") (pintype "bidirectional"))
      (node (ref "U$3") (pin "4") (pinfunction "I_4") (pintype "input"))
    )
    (net (code "13") (name "/TIN2") (class "Default")
      (node (ref "IC9") (pin "5") (pinfunction "+IN_5") (pintype "input"))
      (node (ref "U$1") (pin "PB1") (pinfunction "PB1_PB1") (pintype "bidirectional"))
      (node (ref "U$2") (pin "2") (pinfunction "I_2") (pintype "input"))
    )
    (net (code "14") (name "/TIN5") (class "Default")
      (node (ref "IC6") (pin "3") (pinfunction "+IN_3") (pintype "input"))
      (node (ref "U$1") (pin "PA4") (pinfunction "PA4_PA4") (pintype "bidirectional"))
      (node (ref "U$5") (pin "4") (pinfunction "I_4") (pintype "input"))
    )
    (net (code "15") (name "/TIN6") (class "Default")
      (node (ref "IC6") (pin "5") (pinfunction "+IN_5") (pintype "input"))
      (node (ref "U$1") (pin "PC0") (pinfunction "PC0_PC0") (pintype "bidirectional"))
      (node (ref "U$4") (pin "2") (pinfunction "I_2") (pintype "input"))
    )
    (net (code "16") (name "/TIN7") (class "Default")
      (node (ref "IC6") (pin "10") (pinfunction "+IN_10") (pintype "input"))
      (node (ref "U$1") (pin "PC3") (pinfunction "PC3_PC3") (pintype "bidirectional"))
      (node (ref "U$4") (pin "4") (pinfunction "I_4") (pintype "input"))
    )
    (net (code "17") (name "/TIN8") (class "Default")
      (node (ref "IC6") (pin "12") (pinfunction "+IN_12") (pintype "input"))
      (node (ref "U$1") (pin "PA0") (pinfunction "PA0_PA0") (pintype "bidirectional"))
      (node (ref "U$5") (pin "2") (pinfunction "I_2") (pintype "input"))
    )
    (net (code "18") (name "/U5V") (class "Default")
      (node (ref "U$1") (pin "U5V") (pinfunction "U5V_U5V") (pintype "power_in"))
    )
    (net (code "19") (name "/VBAT") (class "Default")
      (node (ref "U$1") (pin "VBAT") (pinfunction "VBAT_VBAT") (pintype "power_in"))
    )
    (net (code "20") (name "/VDD") (class "Default")
      (node (ref "U$1") (pin "VDD") (pinfunction "VDD_VDD") (pintype "power_in"))
    )
    (net (code "21") (name "CANRX") (class "Default")
      (node (ref "IC7") (pin "4") (pinfunction "RXD_4") (pintype "output"))
      (node (ref "U$1") (pin "PB8") (pinfunction "PB8_PB8") (pintype "bidirectional"))
      (node (ref "U$6") (pin "4") (pinfunction "RXD_4") (pintype "bidirectional"))
    )
    (net (code "22") (name "CANTX") (class "Default")
      (node (ref "IC7") (pin "1") (pinfunction "TXD_1") (pintype "input"))
      (node (ref "U$1") (pin "PB9") (pinfunction "PB9_PB9") (pintype "bidirectional"))
      (node (ref "U$6") (pin "1") (pinfunction "TXD_1") (pintype "bidirectional"))
    )
    (net (code "23") (name "E_CS") (class "Default")
      (node (ref "JP9") (pin "4") (pinfunction "4_4") (pintype "passive"))
      (node (ref "R23") (pin "2") (pinfunction "2_2") (pintype "passive"))
      (node (ref "U$1") (pin "PC10") (pinfunction "PC10_PC10") (pintype "bidirectional"))
    )
    (net (code "24") (name "E_LAT") (class "Default")
      (node (ref "JP10") (pin "1") (pinfunction "1_1") (pintype "passive"))
      (node (ref "R22") (pin "2") (pinfunction "2_2") (pintype "passive"))
      (node (ref "U$1") (pin "PC11") (pinfunction "PC11_PC11") (pintype "bidirectional"))
    )
    (net (code "25") (name "GND") (class "Default")
      (node (ref "AP1509") (pin "4") (pinfunction "SD_4") (pintype "bidirectional"))
      (node (ref "AP1509") (pin "5") (pinfunction "GND1_5") (pintype "power_in"))
      (node (ref "AP1509") (pin "6") (pinfunction "GND2_6") (pintype "power_in"))
      (node (ref "AP1509") (pin "7") (pinfunction "GND3_7") (pintype "power_in"))
      (node (ref "AP1509") (pin "8") (pinfunction "GND4_8") (pintype "power_in"))
      (node (ref "C1") (pin "2") (pinfunction "2_2") (pintype "passive"))
      (node (ref "C12") (pin "2") (pinfunction "2_2") (pintype "passive"))
      (node (ref "C2") (pin "-") (pinfunction "-_-") (pintype "passive"))
      (node (ref "C3") (pin "2") (pinfunction "2_2") (pintype "passive"))
      (node (ref "C4") (pin "2") (pinfunction "2_2") (pintype "passive"))
      (node (ref "C5") (pin "2") (pinfunction "2_2") (pintype "passive"))
      (node (ref "C6") (pin "2") (pinfunction "2_2") (pintype "passive"))
      (node (ref "C7") (pin "2") (pinfunction "2_2") (pintype "passive"))
      (node (ref "D1") (pin "A") (pinfunction "A_A") (pintype "passive"))
      (node (ref "IC1") (pin "6") (pinfunction "INH_6") (pintype "input"))
      (node (ref "IC1") (pin "8") (pinfunction "GND_8") (pintype "power_in"))
      (node (ref "IC10") (pin "2") (pinfunction "GNDSIG_2") (pintype "input"))
      (node (ref "IC10") (pin "3") (pinfunction "~{ON/OFF}_3") (pintype "input"))
      (node (ref "IC10") (pin "4") (pinfunction "GND_4") (pintype "power_in"))
      (node (ref "IC3") (pin "13") (pinfunction "G_13") (pintype "input"))
      (node (ref "IC3") (pin "8") (pinfunction "GND_8") (pintype "power_in"))
      (node (ref "IC4") (pin "6") (pinfunction "INH_6") (pintype "input"))
      (node (ref "IC4") (pin "8") (pinfunction "GND_8") (pintype "power_in"))
      (node (ref "IC5") (pin "13") (pinfunction "G_13") (pintype "input"))
      (node (ref "IC5") (pin "8") (pinfunction "GND_8") (pintype "power_in"))
      (node (ref "IC6") (pin "11") (pinfunction "V-_11") (pintype "power_in"))
      (node (ref "IC7") (pin "2") (pinfunction "GND_2") (pintype "power_in"))
      (node (ref "IC9") (pin "11") (pinfunction "V-_11") (pintype "power_in"))
      (node (ref "J1") (pin "3") (pinfunction "3_3") (pintype "passive"))
      (node (ref "J1") (pin "6") (pinfunction "6_6") (pintype "passive"))
      (node (ref "J1") (pin "7") (pinfunction "7_7") (pintype "passive"))
      (node (ref "J2") (pin "3") (pinfunction "3_3") (pintype "passive"))
      (node (ref "J2") (pin "6") (pinfunction "6_6") (pintype "passive"))
      (node (ref "J2") (pin "7") (pinfunction "7_7") (pintype "passive"))
      (node (ref "J3") (pin "1") (pinfunction "1_1") (pintype "passive"))
      (node (ref "JP10") (pin "4") (pinfunction "4_4") (pintype "passive"))
      (node (ref "JP11") (pin "5") (pinfunction "5_5") (pintype "passive"))
      (node (ref "JP11") (pin "6") (pinfunction "6_6") (pintype "passive"))
      (node (ref "JP13") (pin "5") (pinfunction "5_5") (pintype "passive"))
      (node (ref "JP14") (pin "5") (pinfunction "5_5") (pintype "passive"))
      (node (ref "JP15") (pin "5") (pinfunction "5_5") (pintype "passive"))
      (node (ref "JP7") (pin "5") (pinfunction "5_5") (pintype "passive"))
      (node (ref "JP7") (pin "6") (pinfunction "6_6") (pintype "passive"))
      (node (ref "JP8") (pin "4") (pinfunction "4_4") (pintype "passive"))
      (node (ref "Q1") (pin "2") (pinfunction "S_2") (pintype "passive"))
      (node (ref "Q10") (pin "2") (pinfunction "S_2") (pintype "passive"))
      (node (ref "Q11") (pin "2") (pinfunction "S_2") (pintype "passive"))
      (node (ref "Q12") (pin "2") (pinfunction "S_2") (pintype "passive"))
      (node (ref "Q13") (pin "2") (pinfunction "S_2") (pintype "passive"))
      (node (ref "Q14") (pin "2") (pinfunction "S_2") (pintype "passive"))
      (node (ref "Q15") (pin "2") (pinfunction "S_2") (pintype "passive"))
      (node (ref "Q16") (pin "2") (pinfunction "S_2") (pintype "passive"))
      (node (ref "Q2") (pin "2") (pinfunction "S_2") (pintype "passive"))
      (node (ref "Q3") (pin "2") (pinfunction "S_2") (pintype "passive"))
      (node (ref "Q4") (pin "2") (pinfunction "S_2") (pintype "passive"))
      (node (ref "Q5") (pin "2") (pinfunction "S_2") (pintype "passive"))
      (node (ref "Q6") (pin "2") (pinfunction "S_2") (pintype "passive"))
      (node (ref "Q7") (pin "2") (pinfunction "S_2") (pintype "passive"))
      (node (ref "Q8") (pin "2") (pinfunction "S_2") (pintype "passive"))
      (node (ref "Q9") (pin "2") (pinfunction "S_2") (pintype "passive"))
      (node (ref "R2") (pin "1") (pinfunction "1_1") (pintype "passive"))
      (node (ref "R61") (pin "2") (pinfunction "2_2") (pintype "passive"))
      (node (ref "SJ12") (pin "2") (pinfunction "2_2") (pintype "passive"))
      (node (ref "SJ3") (pin "2") (pinfunction "2_2") (pintype "passive"))
      (node (ref "SJ6") (pin "2") (pinfunction "2_2") (pintype "passive"))
      (node (ref "SJ9") (pin "2") (pinfunction "2_2") (pintype "passive"))
      (node (ref "U$1") (pin "GND3") (pinfunction "GND3_GND3") (pintype "power_in"))
      (node (ref "U$1") (pin "GND4") (pinfunction "GND4_GND4") (pintype "power_in"))
      (node (ref "U$1") (pin "GND5") (pinfunction "GND5_GND5") (pintype "power_in"))
      (node (ref "U$1") (pin "GND6") (pinfunction "GND6_GND6") (pintype "power_in"))
      (node (ref "U$1") (pin "GND7") (pinfunction "GND7_GND7") (pintype "power_in"))
      (node (ref "U$1") (pin "GND8") (pinfunction "GND8_GND8") (pintype "power_in"))
      (node (ref "U$2") (pin "3") (pinfunction "VSS_3") (pintype "power_in"))
      (node (ref "U$3") (pin "3") (pinfunction "VSS_3") (pintype "power_in"))
      (node (ref "U$4") (pin "3") (pinfunction "VSS_3") (pintype "power_in"))
      (node (ref "U$5") (pin "3") (pinfunction "VSS_3") (pintype "power_in"))
      (node (ref "U$6") (pin "2") (pinfunction "VSS_2") (pintype "power_in"))
    )
    (net (code "26") (name "I2CSCL") (class "Default")
      (node (ref "JP8") (pin "2") (pinfunction "2_2") (pintype "passive"))
      (node (ref "U$1") (pin "PB6") (pinfunction "PB6_PB6") (pintype "bidirectional"))
    )
    (net (code "27") (name "I2CSDA") (class "Default")
      (node (ref "JP8") (pin "1") (pinfunction "1_1") (pintype "passive"))
      (node (ref "U$1") (pin "PB7") (pinfunction "PB7_PB7") (pintype "bidirectional"))
    )
    (net (code "28") (name "ILAT") (class "Default")
      (node (ref "IC1") (pin "15") (pinfunction "SH/~{LD}_15") (pintype "input"))
      (node (ref "IC4") (pin "15") (pinfunction "SH/~{LD}_15") (pintype "input"))
      (node (ref "U$1") (pin "PA6") (pinfunction "PA6_PA6") (pintype "bidirectional"))
    )
    (net (code "29") (name "MISO") (class "Default")
      (node (ref "JP9") (pin "1") (pinfunction "1_1") (pintype "passive"))
      (node (ref "U$1") (pin "PB4") (pinfunction "PB4_PB4") (pintype "bidirectional"))
    )
    (net (code "30") (name "MISO2") (class "Default")
      (node (ref "IC4") (pin "13") (pinfunction "QH_13") (pintype "output"))
      (node (ref "SJ13") (pin "2") (pinfunction "2_2") (pintype "passive"))
      (node (ref "U$1") (pin "PC2") (pinfunction "PC2_PC2") (pintype "bidirectional"))
    )
    (net (code "31") (name "MOSI") (class "Default")
      (node (ref "IC5") (pin "14") (pinfunction "SER_14") (pintype "input"))
      (node (ref "R20") (pin "1") (pinfunction "1_1") (pintype "passive"))
      (node (ref "SJ15") (pin "1") (pinfunction "1_1") (pintype "passive"))
      (node (ref "SJ17") (pin "2") (pinfunction "2_2") (pintype "passive"))
      (node (ref "U$1") (pin "PB5") (pinfunction "PB5_PB5") (pintype "bidirectional"))
    )
    (net (code "32") (name "Net-(AP1509-VOUT)") (class "Default")
      (node (ref "AP1509") (pin "2") (pinfunction "VOUT_2") (pintype "bidirectional"))
      (node (ref "D1") (pin "C") (pinfunction "C_C") (pintype "passive"))
      (node (ref "IC10") (pin "7") (pinfunction "OUT_7") (pintype "passive"))
      (node (ref "L1") (pin "2") (pinfunction "2_2") (pintype "passive"))
    )
    (net (code "33") (name "Net-(D2-PadA)") (class "Default")
      (node (ref "D2") (pin "A") (pinfunction "A_A") (pintype "passive"))
      (node (ref "JP4") (pin "4") (pinfunction "4_4") (pintype "passive"))
    )
    (net (code "34") (name "Net-(D2-PadC)") (class "Default")
      (node (ref "D2") (pin "C") (pinfunction "C_C") (pintype "passive"))
      (node (ref "JP4") (pin "1") (pinfunction "1_1") (pintype "passive"))
    )
    (net (code "35") (name "Net-(IC1A-A)") (class "Default")
      (node (ref "IC1") (pin "2") (pinfunction "A_2") (pintype "input"))
      (node (ref "R36") (pin "1") (pinfunction "1_1") (pintype "passive"))
      (node (ref "RN4") (pin "9") (pinfunction "2_9") (pintype "passive"))
    )
    (net (code "36") (name "Net-(IC1A-B)") (class "Default")
      (node (ref "IC1") (pin "3") (pinfunction "B_3") (pintype "input"))
      (node (ref "R37") (pin "1") (pinfunction "1_1") (pintype "passive"))
      (node (ref "RN4") (pin "10") (pinfunction "2_10") (pintype "passive"))
    )
    (net (code "37") (name "Net-(IC1A-C)") (class "Default")
      (node (ref "IC1") (pin "4") (pinfunction "C_4") (pintype "input"))
      (node (ref "R38") (pin "1") (pinfunction "1_1") (pintype "passive"))
      (node (ref "RN4") (pin "11") (pinfunction "2_11") (pintype "passive"))
    )
    (net (code "38") (name "Net-(IC1A-D)") (class "Default")
      (node (ref "IC1") (pin "5") (pinfunction "D_5") (pintype "input"))
      (node (ref "R39") (pin "1") (pinfunction "1_1") (pintype "passive"))
      (node (ref "RN4") (pin "12") (pinfunction "2_12") (pintype "passive"))
    )
    (net (code "39") (name "Net-(IC1A-E)") (class "Default")
      (node (ref "IC1") (pin "10") (pinfunction "E_10") (pintype "input"))
      (node (ref "R41") (pin "1") (pinfunction "1_1") (pintype "passive"))
      (node (ref "RN4") (pin "13") (pinfunction "2_13") (pintype "passive"))
    )
    (net (code "40") (name "Net-(IC1A-F)") (class "Default")
      (node (ref "IC1") (pin "11") (pinfunction "F_11") (pintype "input"))
      (node (ref "R42") (pin "1") (pinfunction "1_1") (pintype "passive"))
      (node (ref "RN4") (pin "14") (pinfunction "2_14") (pintype "passive"))
    )
    (net (code "41") (name "Net-(IC1A-G)") (class "Default")
      (node (ref "IC1") (pin "12") (pinfunction "G_12") (pintype "input"))
      (node (ref "R43") (pin "1") (pinfunction "1_1") (pintype "passive"))
      (node (ref "RN4") (pin "15") (pinfunction "2_15") (pintype "passive"))
    )
    (net (code "42") (name "Net-(IC1A-H)") (class "Default")
      (node (ref "IC1") (pin "14") (pinfunction "H_14") (pintype "input"))
      (node (ref "R44") (pin "1") (pinfunction "1_1") (pintype "passive"))
      (node (ref "RN4") (pin "16") (pinfunction "2_16") (pintype "passive"))
    )
    (net (code "43") (name "Net-(IC2-CD+)") (class "Default")
      (node (ref "IC2") (pin "10") (pinfunction "CD+_10") (pintype "passive"))
      (node (ref "SJ4") (pin "1") (pinfunction "1_1") (pintype "passive"))
      (node (ref "SJ5") (pin "1") (pinfunction "1_1") (pintype "passive"))
      (node (ref "SJ6") (pin "1") (pinfunction "1_1") (pintype "passive"))
    )
    (net (code "44") (name "Net-(IC2-GND)") (class "Default")
      (node (ref "IC2") (pin "9") (pinfunction "GND_9") (pintype "power_in"))
      (node (ref "SJ1") (pin "1") (pinfunction "1_1") (pintype "passive"))
      (node (ref "SJ2") (pin "1") (pinfunction "1_1") (pintype "passive"))
      (node (ref "SJ3") (pin "1") (pinfunction "1_1") (pintype "passive"))
    )
    (net (code "45") (name "Net-(IC2-I1)") (class "Default")
      (node (ref "IC2") (pin "1") (pinfunction "I1_1") (pintype "input"))
      (node (ref "IC5") (pin "15") (pinfunction "QA_15") (pintype "tri_state"))
      (node (ref "R3") (pin "1") (pinfunction "1_1") (pintype "passive"))
    )
    (net (code "46") (name "Net-(IC2-I2)") (class "Default")
      (node (ref "IC2") (pin "2") (pinfunction "I2_2") (pintype "input"))
      (node (ref "IC5") (pin "1") (pinfunction "QB_1") (pintype "tri_state"))
      (node (ref "R4") (pin "1") (pinfunction "1_1") (pintype "passive"))
    )
    (net (code "47") (name "Net-(IC2-I3)") (class "Default")
      (node (ref "IC2") (pin "3") (pinfunction "I3_3") (pintype "input"))
      (node (ref "IC5") (pin "2") (pinfunction "QC_2") (pintype "tri_state"))
      (node (ref "R5") (pin "1") (pinfunction "1_1") (pintype "passive"))
    )
    (net (code "48") (name "Net-(IC2-I4)") (class "Default")
      (node (ref "IC2") (pin "4") (pinfunction "I4_4") (pintype "input"))
      (node (ref "IC5") (pin "3") (pinfunction "QD_3") (pintype "tri_state"))
      (node (ref "R6") (pin "1") (pinfunction "1_1") (pintype "passive"))
    )
    (net (code "49") (name "Net-(IC2-I5)") (class "Default")
      (node (ref "IC2") (pin "5") (pinfunction "I5_5") (pintype "input"))
      (node (ref "IC5") (pin "4") (pinfunction "QE_4") (pintype "tri_state"))
      (node (ref "R7") (pin "1") (pinfunction "1_1") (pintype "passive"))
    )
    (net (code "50") (name "Net-(IC2-I6)") (class "Default")
      (node (ref "IC2") (pin "6") (pinfunction "I6_6") (pintype "input"))
      (node (ref "IC5") (pin "5") (pinfunction "QF_5") (pintype "tri_state"))
      (node (ref "R8") (pin "1") (pinfunction "1_1") (pintype "passive"))
    )
    (net (code "51") (name "Net-(IC2-I7)") (class "Default")
      (node (ref "IC2") (pin "7") (pinfunction "I7_7") (pintype "input"))
      (node (ref "IC5") (pin "6") (pinfunction "QG_6") (pintype "tri_state"))
      (node (ref "R9") (pin "1") (pinfunction "1_1") (pintype "passive"))
    )
    (net (code "52") (name "Net-(IC2-I8)") (class "Default")
      (node (ref "IC2") (pin "8") (pinfunction "I8_8") (pintype "input"))
      (node (ref "IC5") (pin "7") (pinfunction "QH_7") (pintype "tri_state"))
      (node (ref "R10") (pin "1") (pinfunction "1_1") (pintype "passive"))
    )
    (net (code "53") (name "Net-(IC2-O1)") (class "Default")
      (node (ref "IC2") (pin "18") (pinfunction "O1_18") (pintype "open_collector"))
      (node (ref "JP1") (pin "1") (pinfunction "1_1") (pintype "passive"))
      (node (ref "Q1") (pin "3") (pinfunction "D_3") (pintype "passive"))
    )
    (net (code "54") (name "Net-(IC2-O2)") (class "Default")
      (node (ref "IC2") (pin "17") (pinfunction "O2_17") (pintype "open_collector"))
      (node (ref "JP1") (pin "2") (pinfunction "2_2") (pintype "passive"))
      (node (ref "Q2") (pin "3") (pinfunction "D_3") (pintype "passive"))
    )
    (net (code "55") (name "Net-(IC2-O3)") (class "Default")
      (node (ref "IC2") (pin "16") (pinfunction "O3_16") (pintype "open_collector"))
      (node (ref "JP1") (pin "3") (pinfunction "3_3") (pintype "passive"))
      (node (ref "Q3") (pin "3") (pinfunction "D_3") (pintype "passive"))
    )
    (net (code "56") (name "Net-(IC2-O4)") (class "Default")
      (node (ref "IC2") (pin "15") (pinfunction "O4_15") (pintype "open_collector"))
      (node (ref "JP1") (pin "4") (pinfunction "4_4") (pintype "passive"))
      (node (ref "Q4") (pin "3") (pinfunction "D_3") (pintype "passive"))
    )
    (net (code "57") (name "Net-(IC2-O5)") (class "Default")
      (node (ref "IC2") (pin "14") (pinfunction "O5_14") (pintype "open_collector"))
      (node (ref "JP1") (pin "5") (pinfunction "5_5") (pintype "passive"))
      (node (ref "Q5") (pin "3") (pinfunction "D_3") (pintype "passive"))
    )
    (net (code "58") (name "Net-(IC2-O6)") (class "Default")
      (node (ref "IC2") (pin "13") (pinfunction "O6_13") (pintype "open_collector"))
      (node (ref "JP1") (pin "6") (pinfunction "6_6") (pintype "passive"))
      (node (ref "Q6") (pin "3") (pinfunction "D_3") (pintype "passive"))
    )
    (net (code "59") (name "Net-(IC2-O7)") (class "Default")
      (node (ref "IC2") (pin "12") (pinfunction "O7_12") (pintype "open_collector"))
      (node (ref "JP1") (pin "7") (pinfunction "7_7") (pintype "passive"))
      (node (ref "Q7") (pin "3") (pinfunction "D_3") (pintype "passive"))
    )
    (net (code "60") (name "Net-(IC2-O8)") (class "Default")
      (node (ref "IC2") (pin "11") (pinfunction "O8_11") (pintype "open_collector"))
      (node (ref "JP1") (pin "8") (pinfunction "8_8") (pintype "passive"))
      (node (ref "Q8") (pin "3") (pinfunction "D_3") (pintype "passive"))
    )
    (net (code "61") (name "Net-(IC3A-QA)") (class "Default")
      (node (ref "IC3") (pin "15") (pinfunction "QA_15") (pintype "tri_state"))
      (node (ref "IC8") (pin "1") (pinfunction "I1_1") (pintype "input"))
      (node (ref "R11") (pin "1") (pinfunction "1_1") (pintype "passive"))
    )
    (net (code "62") (name "Net-(IC3A-QB)") (class "Default")
      (node (ref "IC3") (pin "1") (pinfunction "QB_1") (pintype "tri_state"))
      (node (ref "IC8") (pin "2") (pinfunction "I2_2") (pintype "input"))
      (node (ref "R12") (pin "1") (pinfunction "1_1") (pintype "passive"))
    )
    (net (code "63") (name "Net-(IC3A-QC)") (class "Default")
      (node (ref "IC3") (pin "2") (pinfunction "QC_2") (pintype "tri_state"))
      (node (ref "IC8") (pin "3") (pinfunction "I3_3") (pintype "input"))
      (node (ref "R13") (pin "1") (pinfunction "1_1") (pintype "passive"))
    )
    (net (code "64") (name "Net-(IC3A-QD)") (class "Default")
      (node (ref "IC3") (pin "3") (pinfunction "QD_3") (pintype "tri_state"))
      (node (ref "IC8") (pin "4") (pinfunction "I4_4") (pintype "input"))
      (node (ref "R14") (pin "1") (pinfunction "1_1") (pintype "passive"))
    )
    (net (code "65") (name "Net-(IC3A-QE)") (class "Default")
      (node (ref "IC3") (pin "4") (pinfunction "QE_4") (pintype "tri_state"))
      (node (ref "IC8") (pin "5") (pinfunction "I5_5") (pintype "input"))
      (node (ref "R15") (pin "1") (pinfunction "1_1") (pintype "passive"))
    )
    (net (code "66") (name "Net-(IC3A-QF)") (class "Default")
      (node (ref "IC3") (pin "5") (pinfunction "QF_5") (pintype "tri_state"))
      (node (ref "IC8") (pin "6") (pinfunction "I6_6") (pintype "input"))
      (node (ref "R16") (pin "1") (pinfunction "1_1") (pintype "passive"))
    )
    (net (code "67") (name "Net-(IC3A-QG)") (class "Default")
      (node (ref "IC3") (pin "6") (pinfunction "QG_6") (pintype "tri_state"))
      (node (ref "IC8") (pin "7") (pinfunction "I7_7") (pintype "input"))
      (node (ref "R17") (pin "1") (pinfunction "1_1") (pintype "passive"))
    )
    (net (code "68") (name "Net-(IC3A-QH)") (class "Default")
      (node (ref "IC3") (pin "7") (pinfunction "QH_7") (pintype "tri_state"))
      (node (ref "IC8") (pin "8") (pinfunction "I8_8") (pintype "input"))
      (node (ref "R18") (pin "1") (pinfunction "1_1") (pintype "passive"))
    )
    (net (code "69") (name "Net-(IC4A-A)") (class "Default")
      (node (ref "IC4") (pin "2") (pinfunction "A_2") (pintype "input"))
      (node (ref "R28") (pin "1") (pinfunction "1_1") (pintype "passive"))
      (node (ref "RN1") (pin "9") (pinfunction "2_9") (pintype "passive"))
    )
    (net (code "70") (name "Net-(IC4A-B)") (class "Default")
      (node (ref "IC4") (pin "3") (pinfunction "B_3") (pintype "input"))
      (node (ref "R29") (pin "1") (pinfunction "1_1") (pintype "passive"))
      (node (ref "RN1") (pin "10") (pinfunction "2_10") (pintype "passive"))
    )
    (net (code "71") (name "Net-(IC4A-C)") (class "Default")
      (node (ref "IC4") (pin "4") (pinfunction "C_4") (pintype "input"))
      (node (ref "R30") (pin "1") (pinfunction "1_1") (pintype "passive"))
      (node (ref "RN1") (pin "11") (pinfunction "2_11") (pintype "passive"))
    )
    (net (code "72") (name "Net-(IC4A-D)") (class "Default")
      (node (ref "IC4") (pin "5") (pinfunction "D_5") (pintype "input"))
      (node (ref "R31") (pin "1") (pinfunction "1_1") (pintype "passive"))
      (node (ref "RN1") (pin "12") (pinfunction "2_12") (pintype "passive"))
    )
    (net (code "73") (name "Net-(IC4A-E)") (class "Default")
      (node (ref "IC4") (pin "10") (pinfunction "E_10") (pintype "input"))
      (node (ref "R32") (pin "1") (pinfunction "1_1") (pintype "passive"))
      (node (ref "RN1") (pin "13") (pinfunction "2_13") (pintype "passive"))
    )
    (net (code "74") (name "Net-(IC4A-F)") (class "Default")
      (node (ref "IC4") (pin "11") (pinfunction "F_11") (pintype "input"))
      (node (ref "R33") (pin "1") (pinfunction "1_1") (pintype "passive"))
      (node (ref "RN1") (pin "14") (pinfunction "2_14") (pintype "passive"))
    )
    (net (code "75") (name "Net-(IC4A-G)") (class "Default")
      (node (ref "IC4") (pin "12") (pinfunction "G_12") (pintype "input"))
      (node (ref "R34") (pin "1") (pinfunction "1_1") (pintype "passive"))
      (node (ref "RN1") (pin "15") (pinfunction "2_15") (pintype "passive"))
    )
    (net (code "76") (name "Net-(IC4A-H)") (class "Default")
      (node (ref "IC4") (pin "14") (pinfunction "H_14") (pintype "input"))
      (node (ref "R35") (pin "1") (pinfunction "1_1") (pintype "passive"))
      (node (ref "RN1") (pin "16") (pinfunction "2_16") (pintype "passive"))
    )
    (net (code "77") (name "Net-(IC6A--IN)") (class "Default")
      (node (ref "IC6") (pin "13") (pinfunction "-IN_13") (pintype "input"))
      (node (ref "IC6") (pin "2") (pinfunction "-IN_2") (pintype "input"))
      (node (ref "IC6") (pin "6") (pinfunction "-IN_6") (pintype "input"))
      (node (ref "IC6") (pin "9") (pinfunction "-IN_9") (pintype "input"))
      (node (ref "IC9") (pin "13") (pinfunction "-IN_13") (pintype "input"))
      (node (ref "IC9") (pin "2") (pinfunction "-IN_2") (pintype "input"))
      (node (ref "IC9") (pin "6") (pinfunction "-IN_6") (pintype "input"))
      (node (ref "IC9") (pin "9") (pinfunction "-IN_9") (pintype "input"))
      (node (ref "R1") (pin "1") (pinfunction "1_1") (pintype "passive"))
      (node (ref "R2") (pin "2") (pinfunction "2_2") (pintype "passive"))
    )
    (net (code "78") (name "Net-(IC6A-OUT)") (class "Default")
      (node (ref "IC6") (pin "1") (pinfunction "OUT_1") (pintype "output"))
      (node (ref "JP15") (pin "3") (pinfunction "3_3") (pintype "passive"))
      (node (ref "JP5") (pin "3") (pinfunction "3_3") (pintype "passive"))
      (node (ref "U$5") (pin "5") (pinfunction "O_5") (pintype "output"))
    )
    (net (code "79") (name "Net-(IC6B-OUT)") (class "Default")
      (node (ref "IC6") (pin "7") (pinfunction "OUT_7") (pintype "output"))
      (node (ref "JP15") (pin "1") (pinfunction "1_1") (pintype "passive"))
      (node (ref "JP5") (pin "1") (pinfunction "1_1") (pintype "passive"))
      (node (ref "U$4") (pin "7") (pinfunction "O_7") (pintype "output"))
    )
    (net (code "80") (name "Net-(IC6C-OUT)") (class "Default")
      (node (ref "IC6") (pin "8") (pinfunction "OUT_8") (pintype "output"))
      (node (ref "JP15") (pin "2") (pinfunction "2_2") (pintype "passive"))
      (node (ref "JP5") (pin "2") (pinfunction "2_2") (pintype "passive"))
      (node (ref "U$4") (pin "5") (pinfunction "O_5") (pintype "output"))
    )
    (net (code "81") (name "Net-(IC6D-OUT)") (class "Default")
      (node (ref "IC6") (pin "14") (pinfunction "OUT_14") (pintype "output"))
      (node (ref "JP15") (pin "4") (pinfunction "4_4") (pintype "passive"))
      (node (ref "JP5") (pin "4") (pinfunction "4_4") (pintype "passive"))
      (node (ref "U$5") (pin "7") (pinfunction "O_7") (pintype "output"))
    )
    (net (code "82") (name "Net-(IC7-RS)") (class "Default")
      (node (ref "IC7") (pin "8") (pinfunction "RS_8") (pintype "input"))
      (node (ref "R61") (pin "1") (pinfunction "1_1") (pintype "passive"))
      (node (ref "U$6") (pin "8") (pinfunction "RS_8") (pintype "bidirectional"))
    )
    (net (code "83") (name "Net-(IC7-VREF)") (class "Default")
      (node (ref "IC7") (pin "5") (pinfunction "VREF_5") (pintype "output"))
      (node (ref "SJ18") (pin "2") (pinfunction "2_2") (pintype "passive"))
      (node (ref "U$6") (pin "5") (pinfunction "VREF_5") (pintype "bidirectional"))
    )
    (net (code "84") (name "Net-(IC8-CD+)") (class "Default")
      (node (ref "IC8") (pin "10") (pinfunction "CD+_10") (pintype "passive"))
      (node (ref "SJ10") (pin "1") (pinfunction "1_1") (pintype "passive"))
      (node (ref "SJ11") (pin "1") (pinfunction "1_1") (pintype "passive"))
      (node (ref "SJ12") (pin "1") (pinfunction "1_1") (pintype "passive"))
    )
    (net (code "85") (name "Net-(IC8-GND)") (class "Default")
      (node (ref "IC8") (pin "9") (pinfunction "GND_9") (pintype "power_in"))
      (node (ref "SJ7") (pin "1") (pinfunction "1_1") (pintype "passive"))
      (node (ref "SJ8") (pin "1") (pinfunction "1_1") (pintype "passive"))
      (node (ref "SJ9") (pin "1") (pinfunction "1_1") (pintype "passive"))
    )
    (net (code "86") (name "Net-(IC8-O1)") (class "Default")
      (node (ref "IC8") (pin "18") (pinfunction "O1_18") (pintype "open_collector"))
      (node (ref "JP6") (pin "1") (pinfunction "1_1") (pintype "passive"))
      (node (ref "Q9") (pin "3") (pinfunction "D_3") (pintype "passive"))
    )
    (net (code "87") (name "Net-(IC8-O2)") (class "Default")
      (node (ref "IC8") (pin "17") (pinfunction "O2_17") (pintype "open_collector"))
      (node (ref "JP6") (pin "2") (pinfunction "2_2") (pintype "passive"))
      (node (ref "Q10") (pin "3") (pinfunction "D_3") (pintype "passive"))
    )
    (net (code "88") (name "Net-(IC8-O3)") (class "Default")
      (node (ref "IC8") (pin "16") (pinfunction "O3_16") (pintype "open_collector"))
      (node (ref "JP6") (pin "3") (pinfunction "3_3") (pintype "passive"))
      (node (ref "Q11") (pin "3") (pinfunction "D_3") (pintype "passive"))
    )
    (net (code "89") (name "Net-(IC8-O4)") (class "Default")
      (node (ref "IC8") (pin "15") (pinfunction "O4_15") (pintype "open_collector"))
      (node (ref "JP6") (pin "4") (pinfunction "4_4") (pintype "passive"))
      (node (ref "Q12") (pin "3") (pinfunction "D_3") (pintype "passive"))
    )
    (net (code "90") (name "Net-(IC8-O5)") (class "Default")
      (node (ref "IC8") (pin "14") (pinfunction "O5_14") (pintype "open_collector"))
      (node (ref "JP6") (pin "5") (pinfunction "5_5") (pintype "passive"))
      (node (ref "Q13") (pin "3") (pinfunction "D_3") (pintype "passive"))
    )
    (net (code "91") (name "Net-(IC8-O6)") (class "Default")
      (node (ref "IC8") (pin "13") (pinfunction "O6_13") (pintype "open_collector"))
      (node (ref "JP6") (pin "6") (pinfunction "6_6") (pintype "passive"))
      (node (ref "Q14") (pin "3") (pinfunction "D_3") (pintype "passive"))
    )
    (net (code "92") (name "Net-(IC8-O7)") (class "Default")
      (node (ref "IC8") (pin "12") (pinfunction "O7_12") (pintype "open_collector"))
      (node (ref "JP6") (pin "7") (pinfunction "7_7") (pintype "passive"))
      (node (ref "Q15") (pin "3") (pinfunction "D_3") (pintype "passive"))
    )
    (net (code "93") (name "Net-(IC8-O8)") (class "Default")
      (node (ref "IC8") (pin "11") (pinfunction "O8_11") (pintype "open_collector"))
      (node (ref "JP6") (pin "8") (pinfunction "8_8") (pintype "passive"))
      (node (ref "Q16") (pin "3") (pinfunction "D_3") (pintype "passive"))
    )
    (net (code "94") (name "Net-(IC9A-OUT)") (class "Default")
      (node (ref "IC9") (pin "1") (pinfunction "OUT_1") (pintype "output"))
      (node (ref "JP15") (pin "9") (pinfunction "9_9") (pintype "passive"))
      (node (ref "JP5") (pin "7") (pinfunction "7_7") (pintype "passive"))
      (node (ref "U$3") (pin "5") (pinfunction "O_5") (pintype "output"))
    )
    (net (code "95") (name "Net-(IC9B-OUT)") (class "Default")
      (node (ref "IC9") (pin "7") (pinfunction "OUT_7") (pintype "output"))
      (node (ref "JP15") (pin "7") (pinfunction "7_7") (pintype "passive"))
      (node (ref "JP5") (pin "5") (pinfunction "5_5") (pintype "passive"))
      (node (ref "U$2") (pin "7") (pinfunction "O_7") (pintype "output"))
    )
    (net (code "96") (name "Net-(IC9C-OUT)") (class "Default")
      (node (ref "IC9") (pin "8") (pinfunction "OUT_8") (pintype "output"))
      (node (ref "JP15") (pin "8") (pinfunction "8_8") (pintype "passive"))
      (node (ref "JP5") (pin "6") (pinfunction "6_6") (pintype "passive"))
      (node (ref "U$2") (pin "5") (pinfunction "O_5") (pintype "output"))
    )
    (net (code "97") (name "Net-(IC9D-OUT)") (class "Default")
      (node (ref "IC9") (pin "14") (pinfunction "OUT_14") (pintype "output"))
      (node (ref "JP15") (pin "10") (pinfunction "10_10") (pintype "passive"))
      (node (ref "JP5") (pin "8") (pinfunction "8_8") (pintype "passive"))
      (node (ref "U$3") (pin "7") (pinfunction "O_7") (pintype "output"))
    )
    (net (code "98") (name "Net-(J1-Pad4)") (class "Default")
      (node (ref "J1") (pin "4") (pinfunction "4_4") (pintype "passive"))
      (node (ref "J2") (pin "4") (pinfunction "4_4") (pintype "passive"))
    )
    (net (code "99") (name "Net-(J1-Pad5)") (class "Default")
      (node (ref "J1") (pin "5") (pinfunction "5_5") (pintype "passive"))
      (node (ref "J2") (pin "5") (pinfunction "5_5") (pintype "passive"))
    )
    (net (code "100") (name "Net-(J1-Pad8)") (class "Default")
      (node (ref "J1") (pin "8") (pinfunction "8_8") (pintype "passive"))
      (node (ref "J2") (pin "8") (pinfunction "8_8") (pintype "passive"))
      (node (ref "R40") (pin "1") (pinfunction "1_1") (pintype "passive"))
    )
    (net (code "101") (name "Net-(JP4-Pad3)") (class "Default")
      (node (ref "JP4") (pin "3") (pinfunction "3_3") (pintype "passive"))
      (node (ref "R40") (pin "2") (pinfunction "2_2") (pintype "passive"))
    )
    (net (code "102") (name "Net-(JP9-Pad2)") (class "Default")
      (node (ref "JP9") (pin "2") (pinfunction "2_2") (pintype "passive"))
      (node (ref "SJ15") (pin "2") (pinfunction "2_2") (pintype "passive"))
      (node (ref "SJ16") (pin "2") (pinfunction "2_2") (pintype "passive"))
    )
    (net (code "103") (name "Net-(JP13-Pad1)") (class "Default")
      (node (ref "JP13") (pin "1") (pinfunction "1_1") (pintype "passive"))
      (node (ref "JP3") (pin "1") (pinfunction "1_1") (pintype "passive"))
      (node (ref "R44") (pin "2") (pinfunction "2_2") (pintype "passive"))
      (node (ref "R53") (pin "2") (pinfunction "2_2") (pintype "passive"))
      (node (ref "RN4") (pin "1") (pinfunction "1_1") (pintype "passive"))
      (node (ref "RN5") (pin "9") (pinfunction "9_9") (pintype "passive"))
    )
    (net (code "104") (name "Net-(JP14-Pad1)") (class "Default")
      (node (ref "JP14") (pin "1") (pinfunction "1_1") (pintype "passive"))
      (node (ref "JP2") (pin "1") (pinfunction "1_1") (pintype "passive"))
      (node (ref "R35") (pin "2") (pinfunction "2_2") (pintype "passive"))
      (node (ref "R45") (pin "2") (pinfunction "2_2") (pintype "passive"))
      (node (ref "RN1") (pin "1") (pinfunction "1_1") (pintype "passive"))
      (node (ref "RN2") (pin "9") (pinfunction "9_9") (pintype "passive"))
    )
    (net (code "105") (name "Net-(Q1-G)") (class "Default")
      (node (ref "Q1") (pin "1") (pinfunction "G_1") (pintype "passive"))
      (node (ref "R3") (pin "2") (pinfunction "2_2") (pintype "passive"))
    )
    (net (code "106") (name "Net-(Q2-G)") (class "Default")
      (node (ref "Q2") (pin "1") (pinfunction "G_1") (pintype "passive"))
      (node (ref "R4") (pin "2") (pinfunction "2_2") (pintype "passive"))
    )
    (net (code "107") (name "Net-(Q3-G)") (class "Default")
      (node (ref "Q3") (pin "1") (pinfunction "G_1") (pintype "passive"))
      (node (ref "R5") (pin "2") (pinfunction "2_2") (pintype "passive"))
    )
    (net (code "108") (name "Net-(Q4-G)") (class "Default")
      (node (ref "Q4") (pin "1") (pinfunction "G_1") (pintype "passive"))
      (node (ref "R6") (pin "2") (pinfunction "2_2") (pintype "passive"))
    )
    (net (code "109") (name "Net-(Q5-G)") (class "Default")
      (node (ref "Q5") (pin "1") (pinfunction "G_1") (pintype "passive"))
      (node (ref "R7") (pin "2") (pinfunction "2_2") (pintype "passive"))
    )
    (net (code "110") (name "Net-(Q6-G)") (class "Default")
      (node (ref "Q6") (pin "1") (pinfunction "G_1") (pintype "passive"))
      (node (ref "R8") (pin "2") (pinfunction "2_2") (pintype "passive"))
    )
    (net (code "111") (name "Net-(Q7-G)") (class "Default")
      (node (ref "Q7") (pin "1") (pinfunction "G_1") (pintype "passive"))
      (node (ref "R9") (pin "2") (pinfunction "2_2") (pintype "passive"))
    )
    (net (code "112") (name "Net-(Q8-G)") (class "Default")
      (node (ref "Q8") (pin "1") (pinfunction "G_1") (pintype "passive"))
      (node (ref "R10") (pin "2") (pinfunction "2_2") (pintype "passive"))
    )
    (net (code "113") (name "Net-(Q9-G)") (class "Default")
      (node (ref "Q9") (pin "1") (pinfunction "G_1") (pintype "passive"))
      (node (ref "R11") (pin "2") (pinfunction "2_2") (pintype "passive"))
    )
    (net (code "114") (name "Net-(Q10-G)") (class "Default")
      (node (ref "Q10") (pin "1") (pinfunction "G_1") (pintype "passive"))
      (node (ref "R12") (pin "2") (pinfunction "2_2") (pintype "passive"))
    )
    (net (code "115") (name "Net-(Q11-G)") (class "Default")
      (node (ref "Q11") (pin "1") (pinfunction "G_1") (pintype "passive"))
      (node (ref "R13") (pin "2") (pinfunction "2_2") (pintype "passive"))
    )
    (net (code "116") (name "Net-(Q12-G)") (class "Default")
      (node (ref "Q12") (pin "1") (pinfunction "G_1") (pintype "passive"))
      (node (ref "R14") (pin "2") (pinfunction "2_2") (pintype "passive"))
    )
    (net (code "117") (name "Net-(Q13-G)") (class "Default")
      (node (ref "Q13") (pin "1") (pinfunction "G_1") (pintype "passive"))
      (node (ref "R15") (pin "2") (pinfunction "2_2") (pintype "passive"))
    )
    (net (code "118") (name "Net-(Q14-G)") (class "Default")
      (node (ref "Q14") (pin "1") (pinfunction "G_1") (pintype "passive"))
      (node (ref "R16") (pin "2") (pinfunction "2_2") (pintype "passive"))
    )
    (net (code "119") (name "Net-(Q15-G)") (class "Default")
      (node (ref "Q15") (pin "1") (pinfunction "G_1") (pintype "passive"))
      (node (ref "R17") (pin "2") (pinfunction "2_2") (pintype "passive"))
    )
    (net (code "120") (name "Net-(Q16-G)") (class "Default")
      (node (ref "Q16") (pin "1") (pinfunction "G_1") (pintype "passive"))
      (node (ref "R18") (pin "2") (pinfunction "2_2") (pintype "passive"))
    )
    (net (code "121") (name "Net-(RN1B-1)") (class "Default")
      (node (ref "JP14") (pin "2") (pinfunction "2_2") (pintype "passive"))
      (node (ref "JP2") (pin "2") (pinfunction "2_2") (pintype "passive"))
      (node (ref "R34") (pin "2") (pinfunction "2_2") (pintype "passive"))
      (node (ref "R46") (pin "1") (pinfunction "1_1") (pintype "passive"))
      (node (ref "RN1") (pin "2") (pinfunction "1_2") (pintype "passive"))
      (node (ref "RN2") (pin "8") (pinfunction "8_8") (pintype "passive"))
    )
    (net (code "122") (name "Net-(RN1C-1)") (class "Default")
      (node (ref "JP14") (pin "3") (pinfunction "3_3") (pintype "passive"))
      (node (ref "JP2") (pin "3") (pinfunction "3_3") (pintype "passive"))
      (node (ref "R33") (pin "2") (pinfunction "2_2") (pintype "passive"))
      (node (ref "R47") (pin "1") (pinfunction "1_1") (pintype "passive"))
      (node (ref "RN1") (pin "3") (pinfunction "1_3") (pintype "passive"))
      (node (ref "RN2") (pin "7") (pinfunction "7_7") (pintype "passive"))
    )
    (net (code "123") (name "Net-(RN1D-1)") (class "Default")
      (node (ref "JP14") (pin "4") (pinfunction "4_4") (pintype "passive"))
      (node (ref "JP2") (pin "4") (pinfunction "4_4") (pintype "passive"))
      (node (ref "R32") (pin "2") (pinfunction "2_2") (pintype "passive"))
      (node (ref "R48") (pin "1") (pinfunction "1_1") (pintype "passive"))
      (node (ref "RN1") (pin "4") (pinfunction "1_4") (pintype "passive"))
      (node (ref "RN2") (pin "6") (pinfunction "6_6") (pintype "passive"))
    )
    (net (code "124") (name "Net-(RN1E-1)") (class "Default")
      (node (ref "JP14") (pin "7") (pinfunction "7_7") (pintype "passive"))
      (node (ref "JP2") (pin "5") (pinfunction "5_5") (pintype "passive"))
      (node (ref "R31") (pin "2") (pinfunction "2_2") (pintype "passive"))
      (node (ref "R49") (pin "1") (pinfunction "1_1") (pintype "passive"))
      (node (ref "RN1") (pin "5") (pinfunction "1_5") (pintype "passive"))
      (node (ref "RN2") (pin "5") (pinfunction "5_5") (pintype "passive"))
    )
    (net (code "125") (name "Net-(RN1F-1)") (class "Default")
      (node (ref "JP14") (pin "8") (pinfunction "8_8") (pintype "passive"))
      (node (ref "JP2") (pin "6") (pinfunction "6_6") (pintype "passive"))
      (node (ref "R30") (pin "2") (pinfunction "2_2") (pintype "passive"))
      (node (ref "R50") (pin "1") (pinfunction "1_1") (pintype "passive"))
      (node (ref "RN1") (pin "6") (pinfunction "1_6") (pintype "passive"))
      (node (ref "RN2") (pin "4") (pinfunction "4_4") (pintype "passive"))
    )
    (net (code "126") (name "Net-(RN1G-1)") (class "Default")
      (node (ref "JP14") (pin "9") (pinfunction "9_9") (pintype "passive"))
      (node (ref "JP2") (pin "7") (pinfunction "7_7") (pintype "passive"))
      (node (ref "R29") (pin "2") (pinfunction "2_2") (pintype "passive"))
      (node (ref "R51") (pin "1") (pinfunction "1_1") (pintype "passive"))
      (node (ref "RN1") (pin "7") (pinfunction "1_7") (pintype "passive"))
      (node (ref "RN2") (pin "3") (pinfunction "3_3") (pintype "passive"))
    )
    (net (code "127") (name "Net-(RN1H-1)") (class "Default")
      (node (ref "JP14") (pin "10") (pinfunction "10_10") (pintype "passive"))
      (node (ref "JP2") (pin "8") (pinfunction "8_8") (pintype "passive"))
      (node (ref "R28") (pin "2") (pinfunction "2_2") (pintype "passive"))
      (node (ref "R52") (pin "1") (pinfunction "1_1") (pintype "passive"))
      (node (ref "RN1") (pin "8") (pinfunction "1_8") (pintype "passive"))
      (node (ref "RN2") (pin "2") (pinfunction "2_2") (pintype "passive"))
    )
    (net (code "128") (name "Net-(RN4B-1)") (class "Default")
      (node (ref "JP13") (pin "2") (pinfunction "2_2") (pintype "passive"))
      (node (ref "JP3") (pin "2") (pinfunction "2_2") (pintype "passive"))
      (node (ref "R43") (pin "2") (pinfunction "2_2") (pintype "passive"))
      (node (ref "R54") (pin "2") (pinfunction "2_2") (pintype "passive"))
      (node (ref "RN4") (pin "2") (pinfunction "1_2") (pintype "passive"))
      (node (ref "RN5") (pin "8") (pinfunction "8_8") (pintype "passive"))
    )
    (net (code "129") (name "Net-(RN4C-1)") (class "Default")
      (node (ref "JP13") (pin "3") (pinfunction "3_3") (pintype "passive"))
      (node (ref "JP3") (pin "3") (pinfunction "3_3") (pintype "passive"))
      (node (ref "R42") (pin "2") (pinfunction "2_2") (pintype "passive"))
      (node (ref "R55") (pin "2") (pinfunction "2_2") (pintype "passive"))
      (node (ref "RN4") (pin "3") (pinfunction "1_3") (pintype "passive"))
      (node (ref "RN5") (pin "7") (pinfunction "7_7") (pintype "passive"))
    )
    (net (code "130") (name "Net-(RN4D-1)") (class "Default")
      (node (ref "JP13") (pin "4") (pinfunction "4_4") (pintype "passive"))
      (node (ref "JP3") (pin "4") (pinfunction "4_4") (pintype "passive"))
      (node (ref "R41") (pin "2") (pinfunction "2_2") (pintype "passive"))
      (node (ref "R56") (pin "2") (pinfunction "2_2") (pintype "passive"))
      (node (ref "RN4") (pin "4") (pinfunction "1_4") (pintype "passive"))
      (node (ref "RN5") (pin "6") (pinfunction "6_6") (pintype "passive"))
    )
    (net (code "131") (name "Net-(RN4E-1)") (class "Default")
      (node (ref "JP13") (pin "7") (pinfunction "7_7") (pintype "passive"))
      (node (ref "JP3") (pin "5") (pinfunction "5_5") (pintype "passive"))
      (node (ref "R39") (pin "2") (pinfunction "2_2") (pintype "passive"))
      (node (ref "R57") (pin "2") (pinfunction "2_2") (pintype "passive"))
      (node (ref "RN4") (pin "5") (pinfunction "1_5") (pintype "passive"))
      (node (ref "RN5") (pin "5") (pinfunction "5_5") (pintype "passive"))
    )
    (net (code "132") (name "Net-(RN4F-1)") (class "Default")
      (node (ref "JP13") (pin "8") (pinfunction "8_8") (pintype "passive"))
      (node (ref "JP3") (pin "6") (pinfunction "6_6") (pintype "passive"))
      (node (ref "R38") (pin "2") (pinfunction "2_2") (pintype "passive"))
      (node (ref "R58") (pin "2") (pinfunction "2_2") (pintype "passive"))
      (node (ref "RN4") (pin "6") (pinfunction "1_6") (pintype "passive"))
      (node (ref "RN5") (pin "4") (pinfunction "4_4") (pintype "passive"))
    )
    (net (code "133") (name "Net-(RN4G-1)") (class "Default")
      (node (ref "JP13") (pin "9") (pinfunction "9_9") (pintype "passive"))
      (node (ref "JP3") (pin "7") (pinfunction "7_7") (pintype "passive"))
      (node (ref "R37") (pin "2") (pinfunction "2_2") (pintype "passive"))
      (node (ref "R59") (pin "2") (pinfunction "2_2") (pintype "passive"))
      (node (ref "RN4") (pin "7") (pinfunction "1_7") (pintype "passive"))
      (node (ref "RN5") (pin "3") (pinfunction "3_3") (pintype "passive"))
    )
    (net (code "134") (name "Net-(RN4H-1)") (class "Default")
      (node (ref "JP13") (pin "10") (pinfunction "10_10") (pintype "passive"))
      (node (ref "JP3") (pin "8") (pinfunction "8_8") (pintype "passive"))
      (node (ref "R36") (pin "2") (pinfunction "2_2") (pintype "passive"))
      (node (ref "R60") (pin "2") (pinfunction "2_2") (pintype "passive"))
      (node (ref "RN4") (pin "8") (pinfunction "1_8") (pintype "passive"))
      (node (ref "RN5") (pin "2") (pinfunction "2_2") (pintype "passive"))
    )
    (net (code "135") (name "Net-(SJ13-Pad1)") (class "Default")
      (node (ref "SJ13") (pin "1") (pinfunction "1_1") (pintype "passive"))
      (node (ref "U$1") (pin "PB14") (pinfunction "PB14_PB14") (pintype "bidirectional"))
    )
    (net (code "136") (name "Net-(SJ14-Pad1)") (class "Default")
      (node (ref "SJ14") (pin "1") (pinfunction "1_1") (pintype "passive"))
      (node (ref "U$1") (pin "VIN2") (pinfunction "VIN2_VIN2") (pintype "power_in"))
    )
    (net (code "137") (name "OLAT") (class "Default")
      (node (ref "IC3") (pin "12") (pinfunction "RCK_12") (pintype "input"))
      (node (ref "IC5") (pin "12") (pinfunction "RCK_12") (pintype "input"))
      (node (ref "R21") (pin "1") (pinfunction "1_1") (pintype "passive"))
      (node (ref "U$1") (pin "PA8") (pinfunction "PA8_PA8") (pintype "bidirectional"))
    )
    (net (code "138") (name "SCK") (class "Default")
      (node (ref "IC3") (pin "11") (pinfunction "SCK_11") (pintype "input"))
      (node (ref "IC5") (pin "11") (pinfunction "SCK_11") (pintype "input"))
      (node (ref "JP9") (pin "3") (pinfunction "3_3") (pintype "passive"))
      (node (ref "R19") (pin "1") (pinfunction "1_1") (pintype "passive"))
      (node (ref "U$1") (pin "PB3") (pinfunction "PB3_PB3") (pintype "bidirectional"))
    )
    (net (code "139") (name "SCK2") (class "Default")
      (node (ref "IC1") (pin "7") (pinfunction "CLK_7") (pintype "input"))
      (node (ref "IC4") (pin "7") (pinfunction "CLK_7") (pintype "input"))
      (node (ref "U$1") (pin "PB10") (pinfunction "PB10_PB10") (pintype "bidirectional"))
    )
    (net (code "140") (name "SLNK1") (class "Default")
      (node (ref "IC3") (pin "14") (pinfunction "SER_14") (pintype "input"))
      (node (ref "IC5") (pin "9") (pinfunction "QH*_9") (pintype "tri_state"))
      (node (ref "SJ17") (pin "1") (pinfunction "1_1") (pintype "passive"))
    )
    (net (code "141") (name "SLNK2") (class "Default")
      (node (ref "IC3") (pin "9") (pinfunction "QH*_9") (pintype "tri_state"))
      (node (ref "SJ16") (pin "1") (pinfunction "1_1") (pintype "passive"))
    )
    (net (code "142") (name "SLNK3") (class "Default")
      (node (ref "IC1") (pin "13") (pinfunction "QH_13") (pintype "output"))
      (node (ref "IC4") (pin "1") (pinfunction "SER_1") (pintype "input"))
    )
    (net (code "143") (name "SRV1") (class "Default")
      (node (ref "JP7") (pin "2") (pinfunction "2_2") (pintype "passive"))
      (node (ref "R25") (pin "2") (pinfunction "2_2") (pintype "passive"))
      (node (ref "U$1") (pin "PC9") (pinfunction "PC9_PC9") (pintype "bidirectional"))
    )
    (net (code "144") (name "SRV2") (class "Default")
      (node (ref "JP7") (pin "1") (pinfunction "1_1") (pintype "passive"))
      (node (ref "R24") (pin "2") (pinfunction "2_2") (pintype "passive"))
      (node (ref "U$1") (pin "PC7") (pinfunction "PC7_PC7") (pintype "bidirectional"))
    )
    (net (code "145") (name "SRV3") (class "Default")
      (node (ref "JP11") (pin "2") (pinfunction "2_2") (pintype "passive"))
      (node (ref "R26") (pin "2") (pinfunction "2_2") (pintype "passive"))
      (node (ref "U$1") (pin "PC8") (pinfunction "PC8_PC8") (pintype "bidirectional"))
    )
    (net (code "146") (name "SRV4") (class "Default")
      (node (ref "JP11") (pin "1") (pinfunction "1_1") (pintype "passive"))
      (node (ref "R27") (pin "2") (pinfunction "2_2") (pintype "passive"))
      (node (ref "U$1") (pin "PC6") (pinfunction "PC6_PC6") (pintype "bidirectional"))
    )
    (net (code "147") (name "TIN3") (class "Default")
      (node (ref "IC9") (pin "10") (pinfunction "+IN_10") (pintype "input"))
      (node (ref "U$1") (pin "PB15") (pinfunction "PB15_PB15") (pintype "bidirectional"))
      (node (ref "U$2") (pin "4") (pinfunction "I_4") (pintype "input"))
    )
    (net (code "148") (name "TIN4") (class "Default")
      (node (ref "IC9") (pin "12") (pinfunction "+IN_12") (pintype "input"))
      (node (ref "U$1") (pin "PB12") (pinfunction "PB12_PB12") (pintype "bidirectional"))
      (node (ref "U$3") (pin "2") (pinfunction "I_2") (pintype "input"))
    )
    (net (code "149") (name "V+") (class "Default")
      (node (ref "AP1509") (pin "3") (pinfunction "FB_3") (pintype "bidirectional"))
      (node (ref "C1") (pin "1") (pinfunction "1_1") (pintype "passive"))
      (node (ref "C2") (pin "+") (pinfunction "+_+") (pintype "passive"))
      (node (ref "IC10") (pin "1") (pinfunction "FB_1") (pintype "input"))
      (node (ref "L1") (pin "1") (pinfunction "1_1") (pintype "passive"))
      (node (ref "U$1") (pin "E5V") (pinfunction "E5V_E5V") (pintype "power_in"))
    )
    (net (code "150") (name "unconnected-(H1-MOUNT-PadB3,3)") (class "Default")
      (node (ref "H1") (pin "B3,3") (pinfunction "MOUNT_B3,3") (pintype "passive"))
    )
    (net (code "151") (name "unconnected-(H2-MOUNT-PadB3,3)") (class "Default")
      (node (ref "H2") (pin "B3,3") (pinfunction "MOUNT_B3,3") (pintype "passive"))
    )
    (net (code "152") (name "unconnected-(H3-MOUNT-PadB3,3)") (class "Default")
      (node (ref "H3") (pin "B3,3") (pinfunction "MOUNT_B3,3") (pintype "passive"))
    )
    (net (code "153") (name "unconnected-(H4-MOUNT-PadB3,3)") (class "Default")
      (node (ref "H4") (pin "B3,3") (pinfunction "MOUNT_B3,3") (pintype "passive"))
    )
    (net (code "154") (name "unconnected-(J3-Pad2)") (class "Default")
      (node (ref "J3") (pin "2") (pinfunction "2_2") (pintype "passive"))
    )
    (net (code "155") (name "unconnected-(U$1-PadBOOT0)") (class "Default")
      (node (ref "U$1") (pin "BOOT0") (pinfunction "BOOT0_BOOT0") (pintype "bidirectional"))
    )
    (net (code "156") (name "unconnected-(U$1-PadIOREF2)") (class "Default")
      (node (ref "U$1") (pin "IOREF2") (pinfunction "IOREF2_IOREF2") (pintype "input"))
    )
    (net (code "157") (name "unconnected-(U$1-PadNC1-PF7)") (class "Default")
      (node (ref "U$1") (pin "NC1-PF7") (pinfunction "NC1-PF7_NC1-PF7") (pintype "bidirectional"))
    )
    (net (code "158") (name "unconnected-(U$1-PadNC2-PF6)") (class "Default")
      (node (ref "U$1") (pin "NC2-PF6") (pinfunction "NC2-PF6_NC2-PF6") (pintype "bidirectional"))
    )
    (net (code "159") (name "unconnected-(U$1-PadNC3)") (class "Default")
      (node (ref "U$1") (pin "NC3") (pinfunction "NC3_NC3") (pintype "no_connect"))
    )
    (net (code "160") (name "unconnected-(U$1-PadNC4)") (class "Default")
      (node (ref "U$1") (pin "NC4") (pinfunction "NC4_NC4") (pintype "no_connect"))
    )
    (net (code "161") (name "unconnected-(U$1-PadNC5-PD8)") (class "Default")
      (node (ref "U$1") (pin "NC5-PD8") (pinfunction "NC5-PD8_NC5-PD8") (pintype "bidirectional"))
    )
    (net (code "162") (name "unconnected-(U$1-PadNC6-PB11)") (class "Default")
      (node (ref "U$1") (pin "NC6-PB11") (pinfunction "NC6-PB11_NC6-PB11") (pintype "no_connect"))
    )
    (net (code "163") (name "unconnected-(U$1-PadNC7-PF5)") (class "Default")
      (node (ref "U$1") (pin "NC7-PF5") (pinfunction "NC7-PF5_NC7-PF5") (pintype "bidirectional"))
    )
    (net (code "164") (name "unconnected-(U$1-PadNC8-PF4)") (class "Default")
      (node (ref "U$1") (pin "NC8-PF4") (pinfunction "NC8-PF4_NC8-PF4") (pintype "bidirectional"))
    )
    (net (code "165") (name "unconnected-(U$1-PadNRESET)") (class "Default")
      (node (ref "U$1") (pin "NRESET") (pinfunction "NRESET_NRESET") (pintype "input"))
    )
    (net (code "166") (name "unconnected-(U$1-PadPA1)") (class "Default")
      (node (ref "U$1") (pin "PA1") (pinfunction "PA1_PA1") (pintype "bidirectional"))
    )
    (net (code "167") (name "unconnected-(U$1-PadPA2)") (class "Default")
      (node (ref "U$1") (pin "PA2") (pinfunction "PA2_PA2") (pintype "bidirectional"))
    )
    (net (code "168") (name "unconnected-(U$1-PadPA3)") (class "Default")
      (node (ref "U$1") (pin "PA3") (pinfunction "PA3_PA3") (pintype "bidirectional"))
    )
    (net (code "169") (name "unconnected-(U$1-PadPA5)") (class "Default")
      (node (ref "U$1") (pin "PA5") (pinfunction "PA5_PA5") (pintype "bidirectional"))
    )
    (net (code "170") (name "unconnected-(U$1-PadPA7)") (class "Default")
      (node (ref "U$1") (pin "PA7") (pinfunction "PA7_PA7") (pintype "bidirectional"))
    )
    (net (code "171") (name "unconnected-(U$1-PadPA9)") (class "Default")
      (node (ref "U$1") (pin "PA9") (pinfunction "PA9_PA9") (pintype "bidirectional"))
    )
    (net (code "172") (name "unconnected-(U$1-PadPA10)") (class "Default")
      (node (ref "U$1") (pin "PA10") (pinfunction "PA10_PA10") (pintype "bidirectional"))
    )
    (net (code "173") (name "unconnected-(U$1-PadPA11)") (class "Default")
      (node (ref "U$1") (pin "PA11") (pinfunction "PA11_PA11") (pintype "bidirectional"))
    )
    (net (code "174") (name "unconnected-(U$1-PadPA12)") (class "Default")
      (node (ref "U$1") (pin "PA12") (pinfunction "PA12_PA12") (pintype "bidirectional"))
    )
    (net (code "175") (name "unconnected-(U$1-PadPA13)") (class "Default")
      (node (ref "U$1") (pin "PA13") (pinfunction "PA13_PA13") (pintype "bidirectional"))
    )
    (net (code "176") (name "unconnected-(U$1-PadPA14)") (class "Default")
      (node (ref "U$1") (pin "PA14") (pinfunction "PA14_PA14") (pintype "bidirectional"))
    )
    (net (code "177") (name "unconnected-(U$1-PadPB0)") (class "Default")
      (node (ref "U$1") (pin "PB0") (pinfunction "PB0_PB0") (pintype "bidirectional"))
    )
    (net (code "178") (name "unconnected-(U$1-PadPB13)") (class "Default")
      (node (ref "U$1") (pin "PB13") (pinfunction "PB13_PB13") (pintype "bidirectional"))
    )
    (net (code "179") (name "unconnected-(U$1-PadPC1)") (class "Default")
      (node (ref "U$1") (pin "PC1") (pinfunction "PC1_PC1") (pintype "bidirectional"))
    )
    (net (code "180") (name "unconnected-(U$1-PadPC4)") (class "Default")
      (node (ref "U$1") (pin "PC4") (pinfunction "PC4_PC4") (pintype "bidirectional"))
    )
    (net (code "181") (name "unconnected-(U$1-PadPC5)") (class "Default")
      (node (ref "U$1") (pin "PC5") (pinfunction "PC5_PC5") (pintype "bidirectional"))
    )
    (net (code "182") (name "unconnected-(U$1-PadPC13)") (class "Default")
      (node (ref "U$1") (pin "PC13") (pinfunction "PC13_PC13") (pintype "bidirectional"))
    )
    (net (code "183") (name "unconnected-(U$1-PadPC14)") (class "Default")
      (node (ref "U$1") (pin "PC14") (pinfunction "PC14_PC14") (pintype "bidirectional"))
    )
    (net (code "184") (name "unconnected-(U$1-PadPC15)") (class "Default")
      (node (ref "U$1") (pin "PC15") (pinfunction "PC15_PC15") (pintype "bidirectional"))
    )
    (net (code "185") (name "unconnected-(U$1-PadPF0-PH0)") (class "Default")
      (node (ref "U$1") (pin "PF0-PH0") (pinfunction "PF0-PH0_PF0-PH0") (pintype "bidirectional"))
    )
  )
)
